# EDCPSUMK1-RP2040.net
KiCad netlist of a schematic drawn in EAGLE
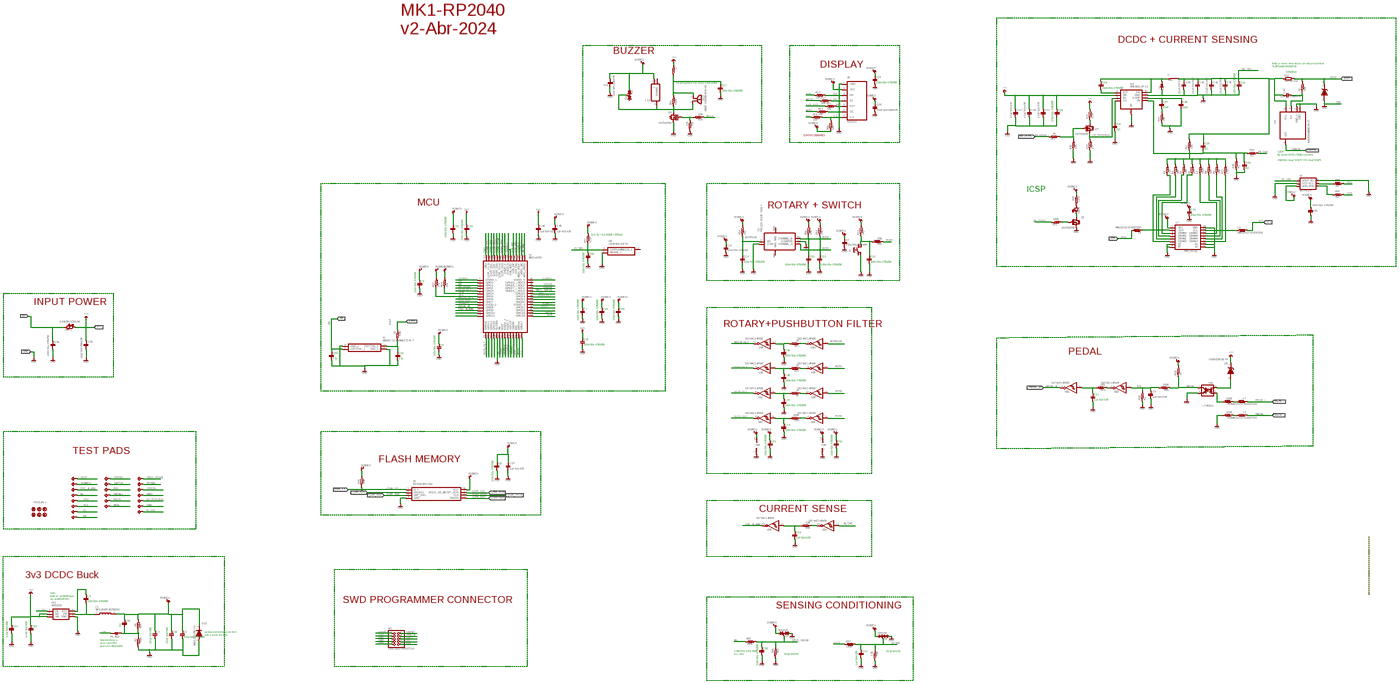
[diagram p0: schematic, sheet 1, overview]
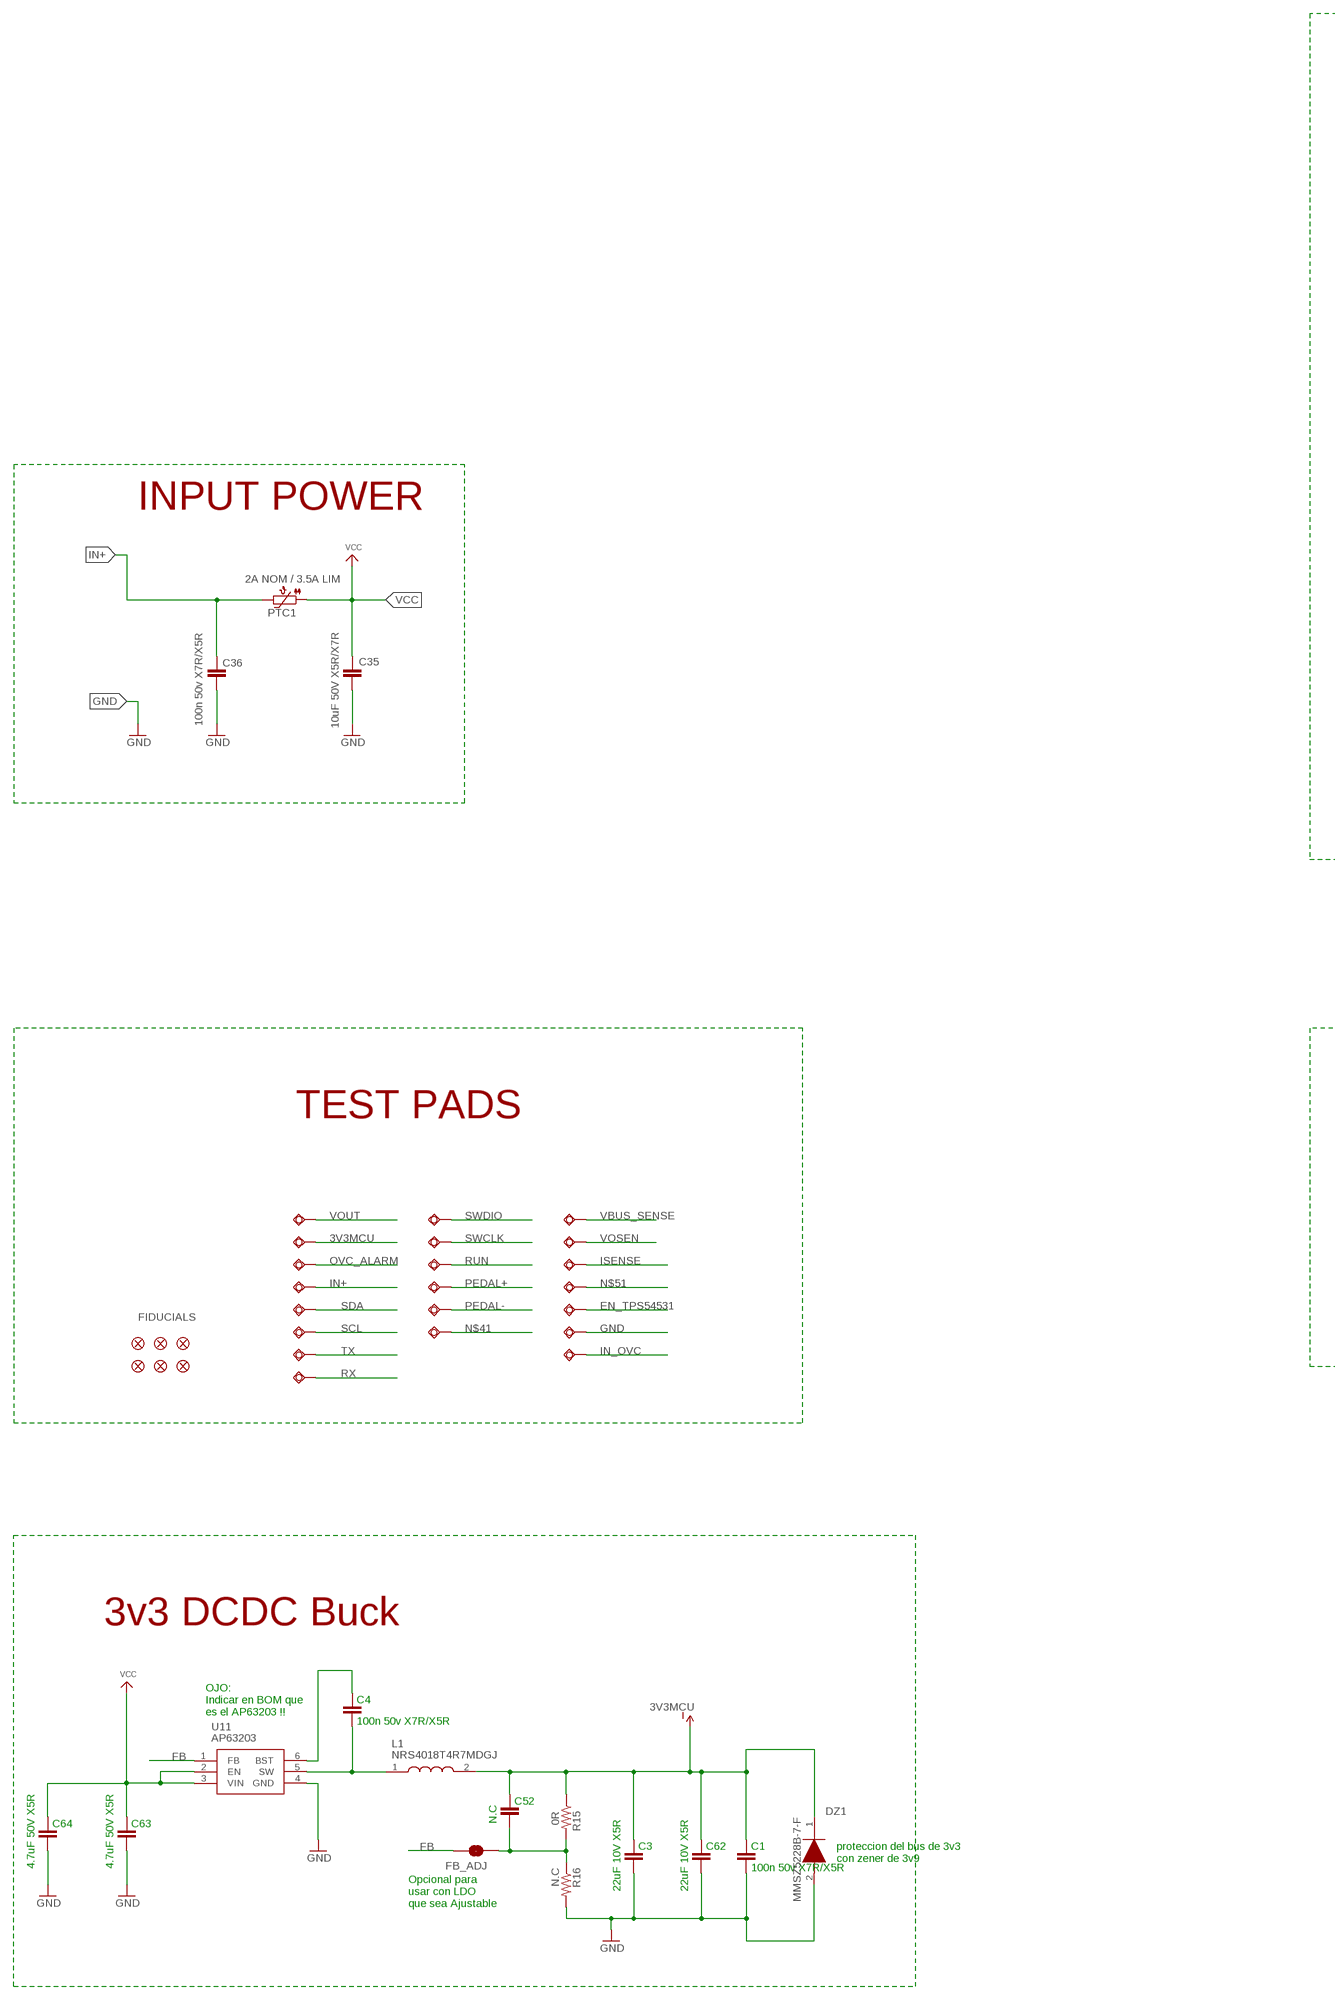
[diagram p1: schematic, sheet 1, part 1 of 5]
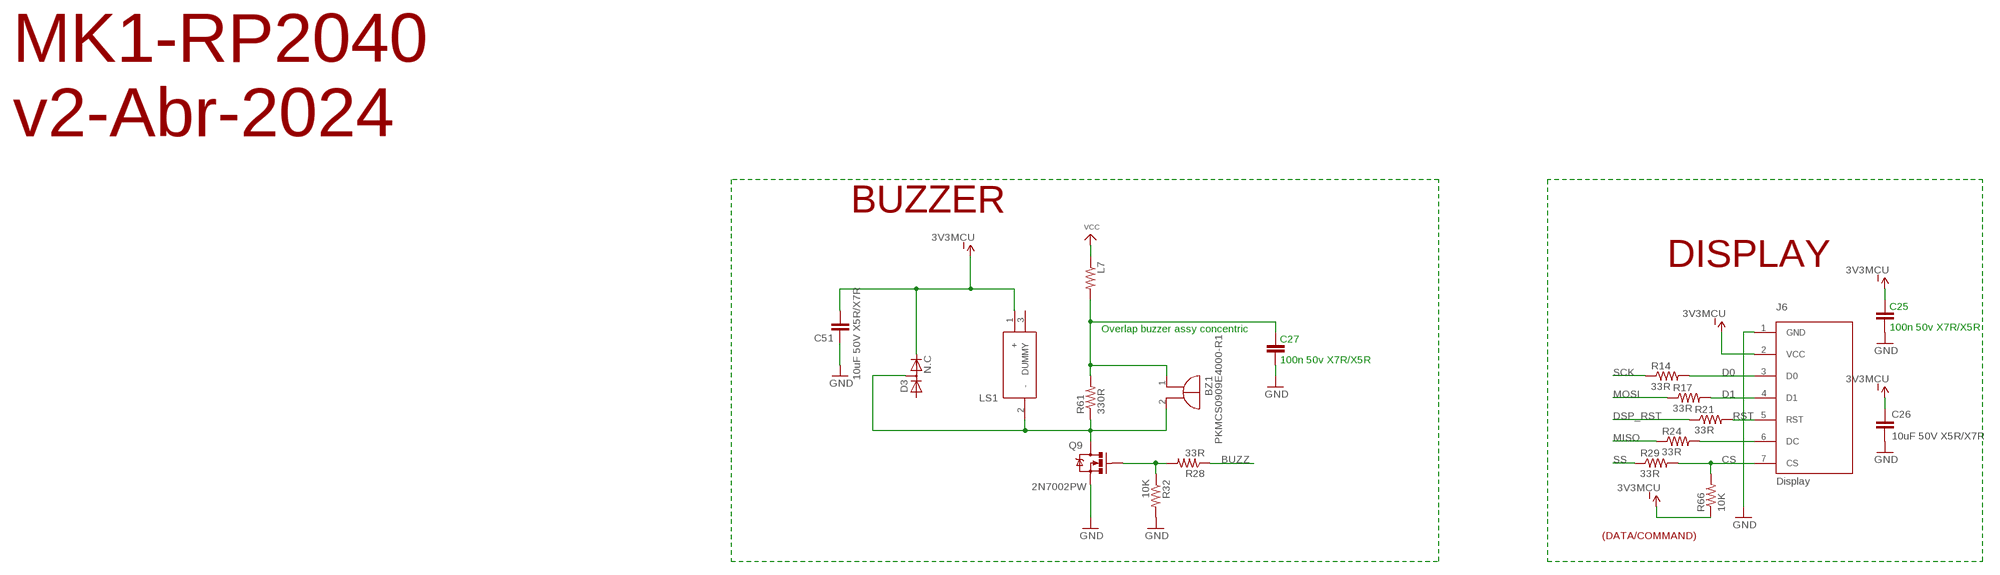
[diagram p2: schematic, sheet 1, part 2 of 5]
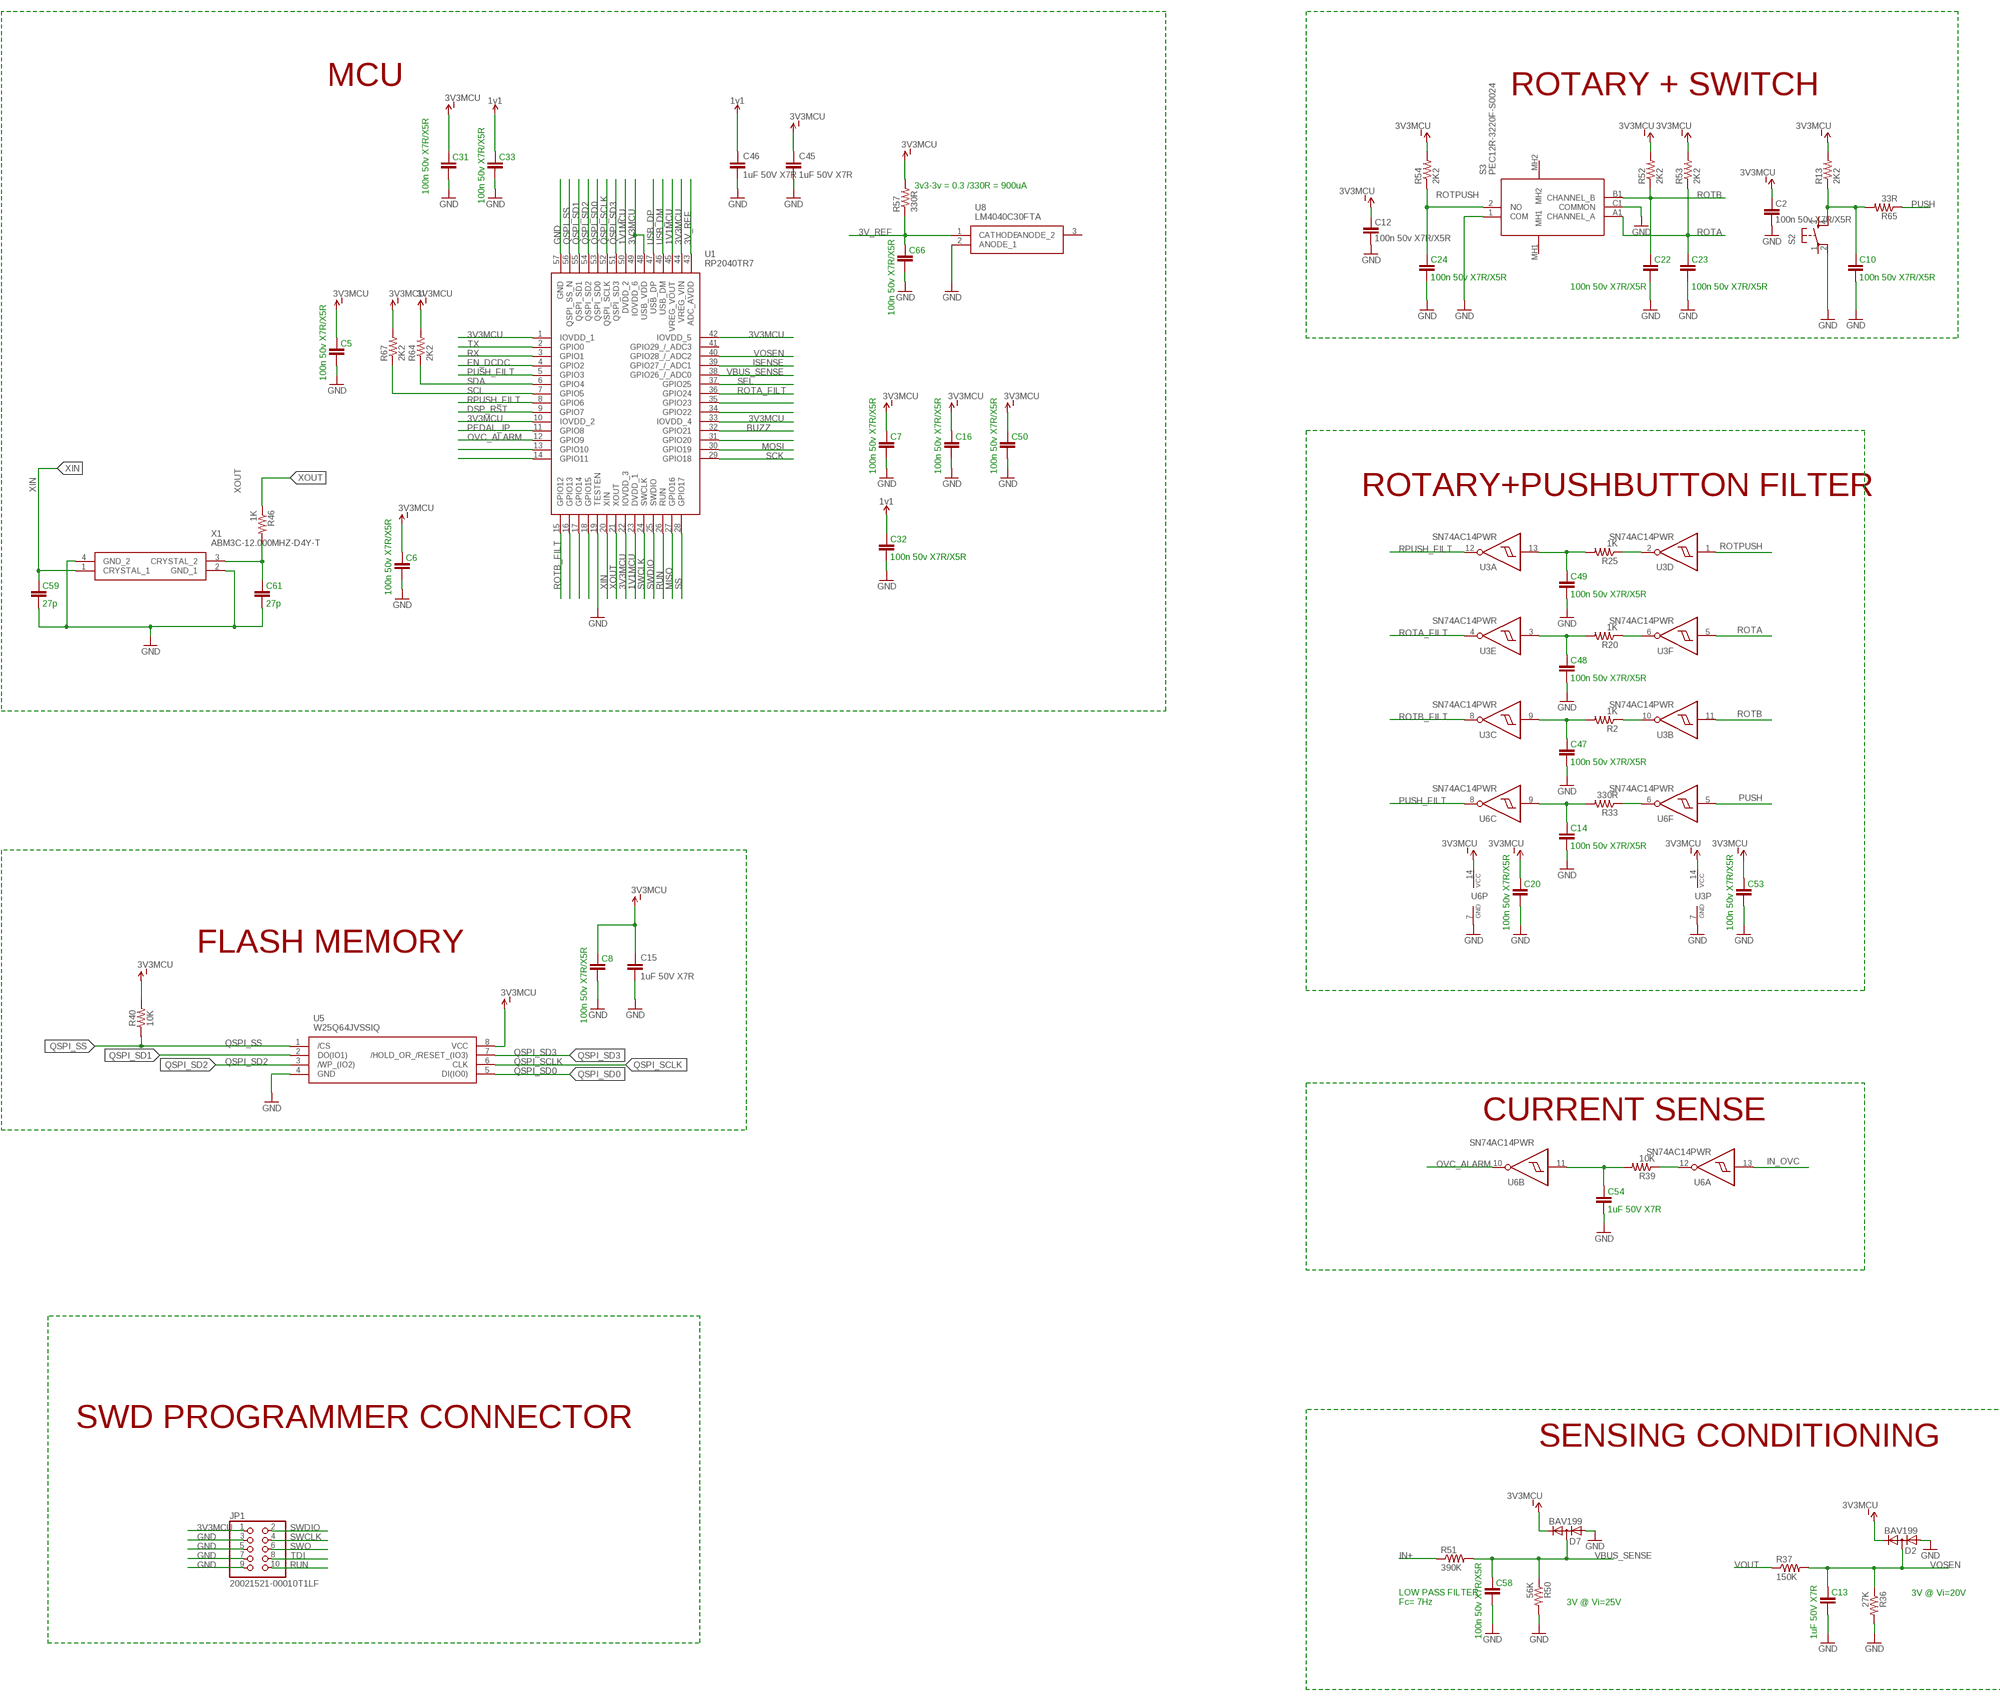
[diagram p3: schematic, sheet 1, part 3 of 5]
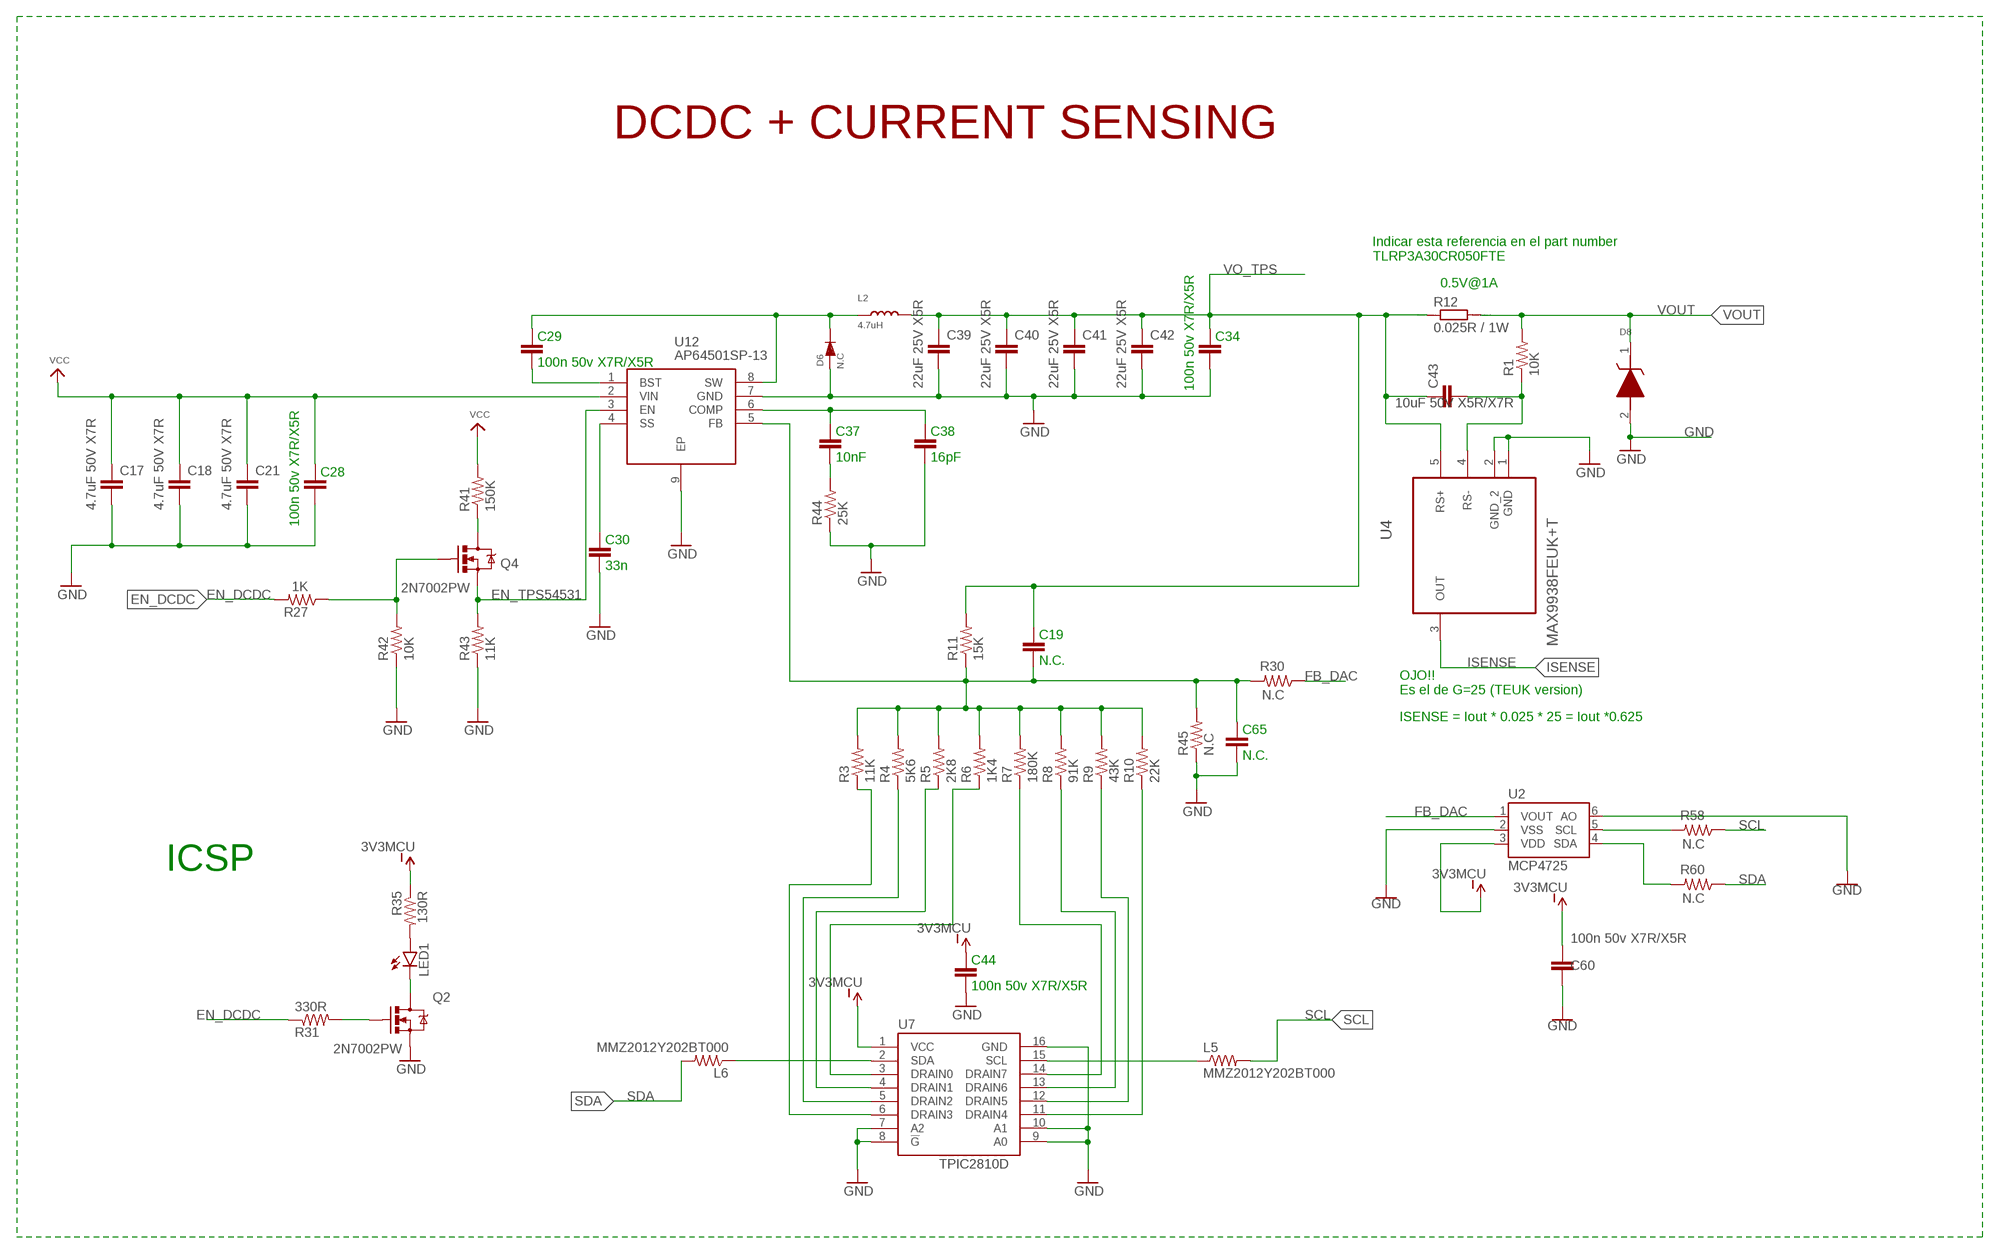
[diagram p4: schematic, sheet 1, part 4 of 5]
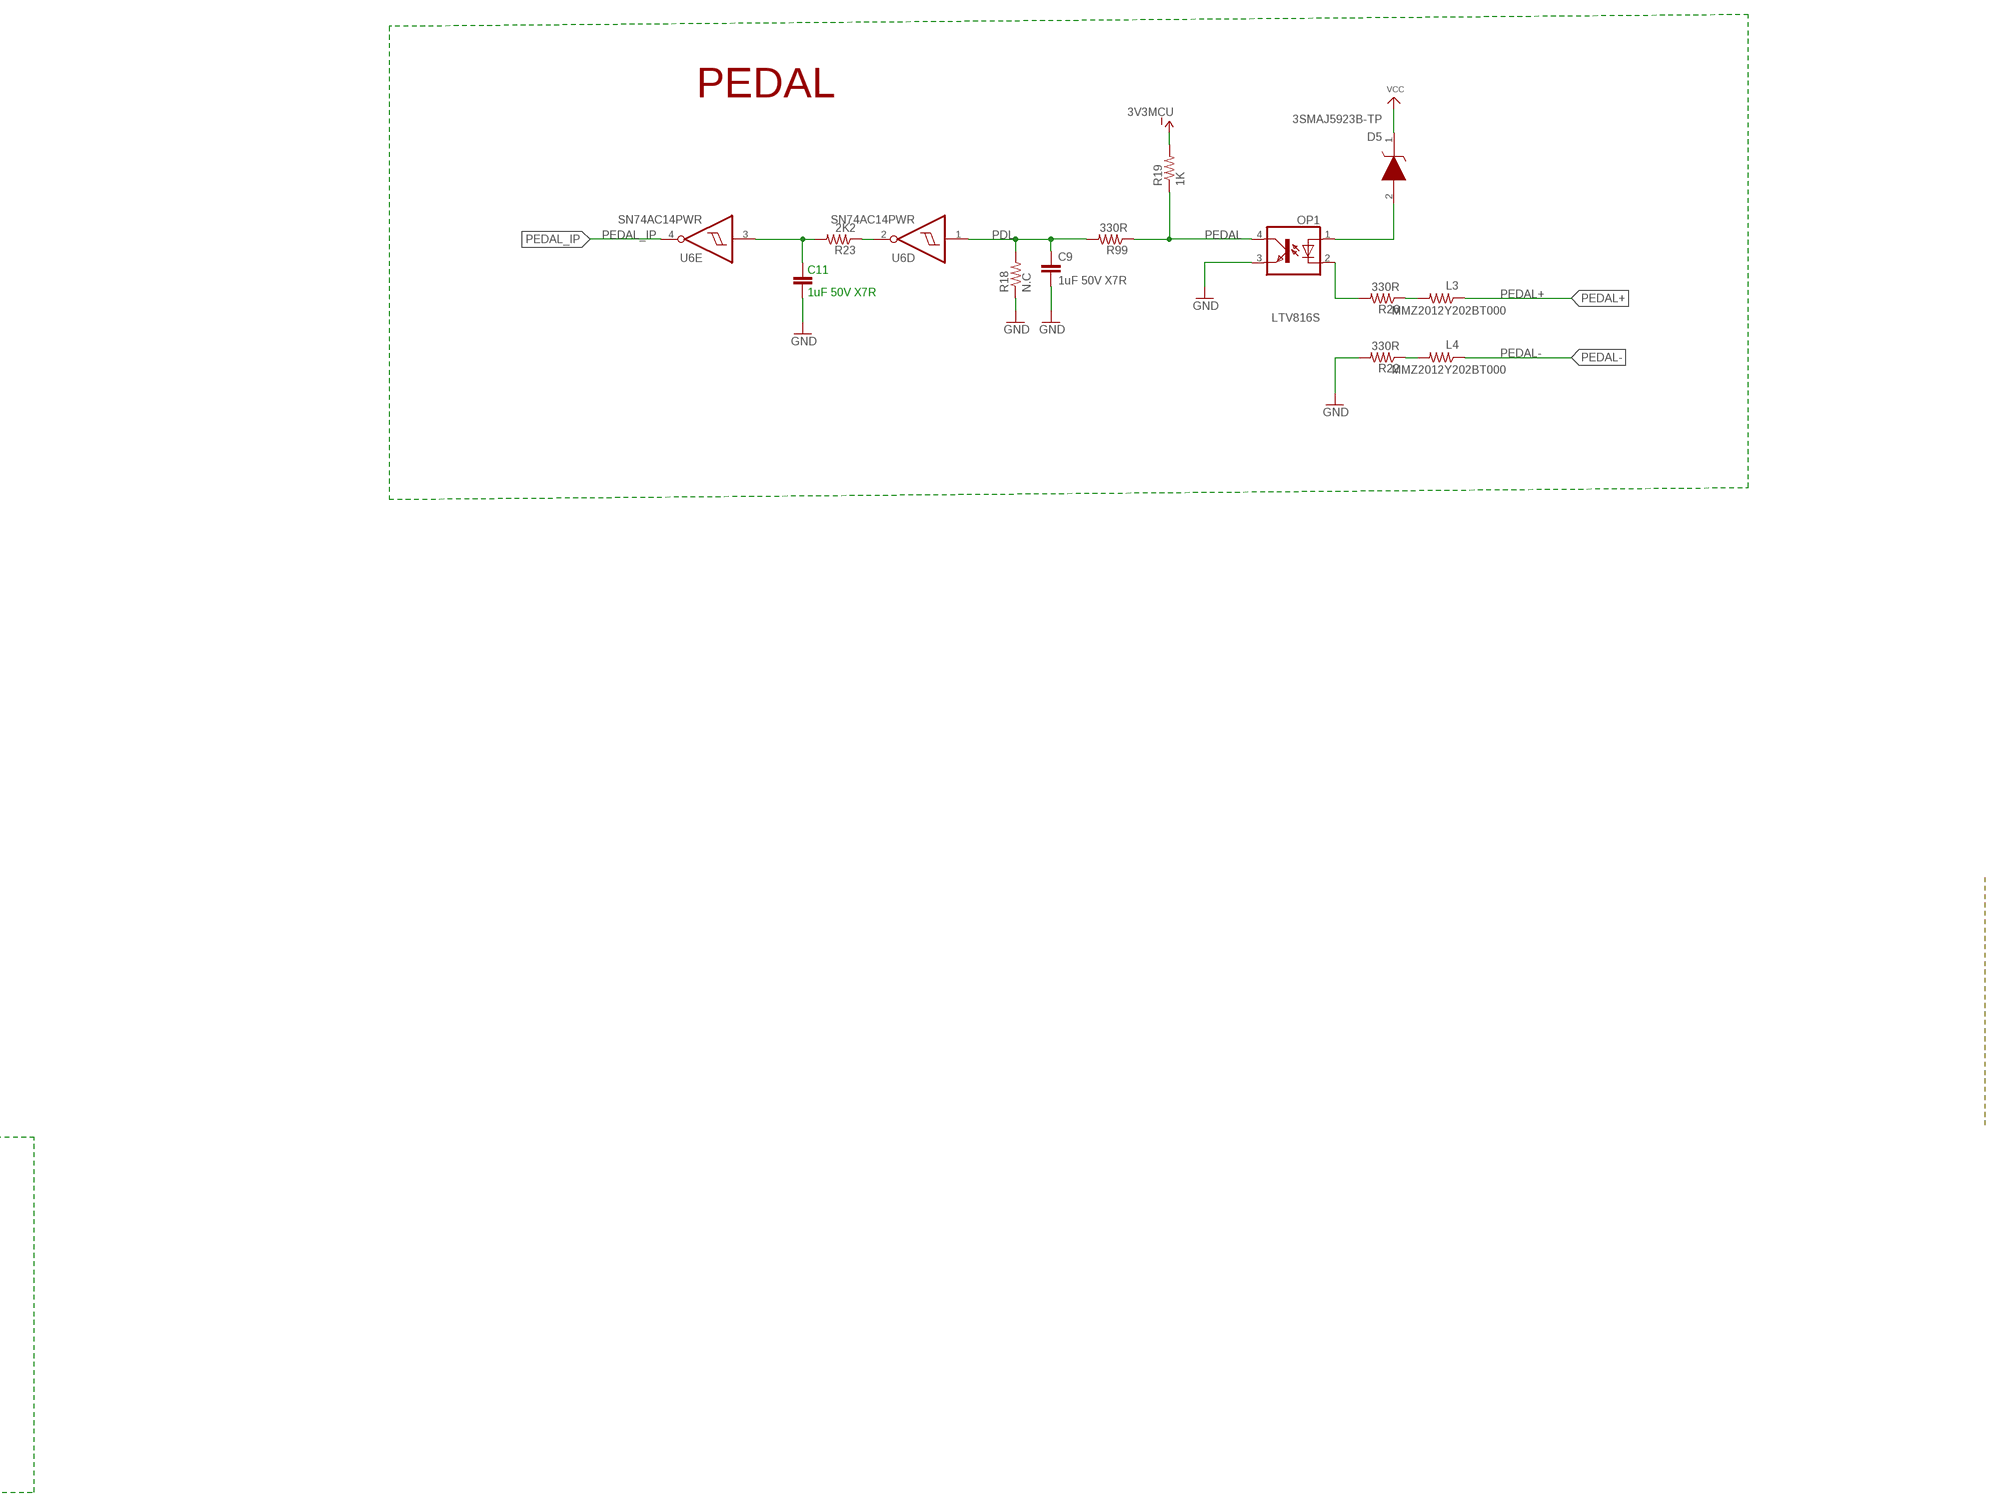
[diagram p5: schematic, sheet 1, part 5 of 5]

(export (version "E")
  (design (tool "Eeschema 10.0.6"))
  (components
    (comp (ref "3V3MCU")
      (value "TESTPAD_TPSQB1,27")
      (footprint "eagle-import:TESTPAD_B1,27")
      (libsource (lib "eagle-import") (part "TESTPAD_TPSQB1,27"))
    )
    (comp (ref "BZ1")
      (value "PKMCS0909E4000-R1")
      (footprint "eagle-import:PKMCS0909")
      (libsource (lib "eagle-import") (part "PKMCS0909E4000-R1"))
    )
    (comp (ref "C1")
      (value "100n 50v X7R/X5R")
      (footprint "eagle-import:0805")
      (libsource (lib "eagle-import") (part "CAP0805"))
    )
    (comp (ref "C2")
      (value "100n 50v X7R/X5R")
      (footprint "eagle-import:0805")
      (libsource (lib "eagle-import") (part "CAP0805"))
    )
    (comp (ref "C3")
      (value "22uF 10V X5R")
      (footprint "eagle-import:0805")
      (libsource (lib "eagle-import") (part "CAP0805"))
    )
    (comp (ref "C4")
      (value "100n 50v X7R/X5R")
      (footprint "eagle-import:0805")
      (libsource (lib "eagle-import") (part "CAP0805"))
    )
    (comp (ref "C5")
      (value "100n 50v X7R/X5R")
      (footprint "eagle-import:0805")
      (libsource (lib "eagle-import") (part "CAP0805"))
    )
    (comp (ref "C6")
      (value "100n 50v X7R/X5R")
      (footprint "eagle-import:0805")
      (libsource (lib "eagle-import") (part "CAP0805"))
    )
    (comp (ref "C7")
      (value "100n 50v X7R/X5R")
      (footprint "eagle-import:0805")
      (libsource (lib "eagle-import") (part "CAP0805"))
    )
    (comp (ref "C8")
      (value "100n 50v X7R/X5R")
      (footprint "eagle-import:0805")
      (libsource (lib "eagle-import") (part "CAP0805"))
    )
    (comp (ref "C9")
      (value "1uF 50V X7R")
      (footprint "eagle-import:0805")
      (libsource (lib "eagle-import") (part "CAP0805"))
    )
    (comp (ref "C10")
      (value "100n 50v X7R/X5R")
      (footprint "eagle-import:0805")
      (libsource (lib "eagle-import") (part "CAP0805"))
    )
    (comp (ref "C11")
      (value "1uF 50V X7R")
      (footprint "eagle-import:0805")
      (libsource (lib "eagle-import") (part "CAP0805"))
    )
    (comp (ref "C12")
      (value "100n 50v X7R/X5R")
      (footprint "eagle-import:0805")
      (libsource (lib "eagle-import") (part "CAP0805"))
    )
    (comp (ref "C13")
      (value "1uF 50V X7R")
      (footprint "eagle-import:0805")
      (libsource (lib "eagle-import") (part "CAP0805"))
    )
    (comp (ref "C14")
      (value "100n 50v X7R/X5R")
      (footprint "eagle-import:0805")
      (libsource (lib "eagle-import") (part "CAP0805"))
    )
    (comp (ref "C15")
      (value "1uF 50V X7R")
      (footprint "eagle-import:0805")
      (libsource (lib "eagle-import") (part "CAP0805"))
    )
    (comp (ref "C16")
      (value "100n 50v X7R/X5R")
      (footprint "eagle-import:0805")
      (libsource (lib "eagle-import") (part "CAP0805"))
    )
    (comp (ref "C17")
      (value "4.7uF 50V X7R")
      (footprint "eagle-import:1210")
      (libsource (lib "eagle-import") (part "CAP1210"))
    )
    (comp (ref "C18")
      (value "4.7uF 50V X7R")
      (footprint "eagle-import:1210")
      (libsource (lib "eagle-import") (part "CAP1210"))
    )
    (comp (ref "C19")
      (value "N.C.")
      (footprint "eagle-import:0805")
      (libsource (lib "eagle-import") (part "CAP0805"))
    )
    (comp (ref "C20")
      (value "100n 50v X7R/X5R")
      (footprint "eagle-import:0805")
      (libsource (lib "eagle-import") (part "CAP0805"))
    )
    (comp (ref "C21")
      (value "4.7uF 50V X7R")
      (footprint "eagle-import:1210")
      (libsource (lib "eagle-import") (part "CAP1210"))
    )
    (comp (ref "C22")
      (value "100n 50v X7R/X5R")
      (footprint "eagle-import:0805")
      (libsource (lib "eagle-import") (part "CAP0805"))
    )
    (comp (ref "C23")
      (value "100n 50v X7R/X5R")
      (footprint "eagle-import:0805")
      (libsource (lib "eagle-import") (part "CAP0805"))
    )
    (comp (ref "C24")
      (value "100n 50v X7R/X5R")
      (footprint "eagle-import:0805")
      (libsource (lib "eagle-import") (part "CAP0805"))
    )
    (comp (ref "C25")
      (value "100n 50v X7R/X5R")
      (footprint "eagle-import:0805")
      (libsource (lib "eagle-import") (part "CAP0805"))
    )
    (comp (ref "C26")
      (value "10uF 50V X5R/X7R")
      (footprint "eagle-import:1206")
      (libsource (lib "eagle-import") (part "CAP1206"))
    )
    (comp (ref "C27")
      (value "100n 50v X7R/X5R")
      (footprint "eagle-import:0805")
      (libsource (lib "eagle-import") (part "CAP0805"))
    )
    (comp (ref "C28")
      (value "100n 50v X7R/X5R")
      (footprint "eagle-import:0805")
      (libsource (lib "eagle-import") (part "CAP0805"))
    )
    (comp (ref "C29")
      (value "100n 50v X7R/X5R")
      (footprint "eagle-import:0805")
      (libsource (lib "eagle-import") (part "CAP0805"))
    )
    (comp (ref "C30")
      (value "33n")
      (footprint "eagle-import:0805")
      (libsource (lib "eagle-import") (part "CAP0805"))
    )
    (comp (ref "C31")
      (value "100n 50v X7R/X5R")
      (footprint "eagle-import:0805")
      (libsource (lib "eagle-import") (part "CAP0805"))
    )
    (comp (ref "C32")
      (value "100n 50v X7R/X5R")
      (footprint "eagle-import:0805")
      (libsource (lib "eagle-import") (part "CAP0805"))
    )
    (comp (ref "C33")
      (value "100n 50v X7R/X5R")
      (footprint "eagle-import:0805")
      (libsource (lib "eagle-import") (part "CAP0805"))
    )
    (comp (ref "C34")
      (value "100n 50v X7R/X5R")
      (footprint "eagle-import:0805")
      (libsource (lib "eagle-import") (part "CAP0805"))
    )
    (comp (ref "C35")
      (value "10uF 50V X5R/X7R")
      (footprint "eagle-import:1206")
      (libsource (lib "eagle-import") (part "CAP1206"))
    )
    (comp (ref "C36")
      (value "100n 50v X7R/X5R")
      (footprint "eagle-import:0805")
      (libsource (lib "eagle-import") (part "CAP0805"))
    )
    (comp (ref "C37")
      (value "10nF")
      (footprint "eagle-import:0805")
      (libsource (lib "eagle-import") (part "CAP0805"))
    )
    (comp (ref "C38")
      (value "16pF")
      (footprint "eagle-import:0805")
      (libsource (lib "eagle-import") (part "CAP0805"))
    )
    (comp (ref "C39")
      (value "22uF 25V X5R")
      (footprint "eagle-import:1210")
      (libsource (lib "eagle-import") (part "CAP1210"))
    )
    (comp (ref "C40")
      (value "22uF 25V X5R")
      (footprint "eagle-import:1210")
      (libsource (lib "eagle-import") (part "CAP1210"))
    )
    (comp (ref "C41")
      (value "22uF 25V X5R")
      (footprint "eagle-import:1210")
      (libsource (lib "eagle-import") (part "CAP1210"))
    )
    (comp (ref "C42")
      (value "22uF 25V X5R")
      (footprint "eagle-import:1210")
      (libsource (lib "eagle-import") (part "CAP1210"))
    )
    (comp (ref "C43")
      (value "10uF 50V X5R/X7R")
      (footprint "eagle-import:1206")
      (libsource (lib "eagle-import") (part "CAP1206"))
    )
    (comp (ref "C44")
      (value "100n 50v X7R/X5R")
      (footprint "eagle-import:0805")
      (libsource (lib "eagle-import") (part "CAP0805"))
    )
    (comp (ref "C45")
      (value "1uF 50V X7R")
      (footprint "eagle-import:0805")
      (libsource (lib "eagle-import") (part "CAP0805"))
    )
    (comp (ref "C46")
      (value "1uF 50V X7R")
      (footprint "eagle-import:0805")
      (libsource (lib "eagle-import") (part "CAP0805"))
    )
    (comp (ref "C47")
      (value "100n 50v X7R/X5R")
      (footprint "eagle-import:0805")
      (libsource (lib "eagle-import") (part "CAP0805"))
    )
    (comp (ref "C48")
      (value "100n 50v X7R/X5R")
      (footprint "eagle-import:0805")
      (libsource (lib "eagle-import") (part "CAP0805"))
    )
    (comp (ref "C49")
      (value "100n 50v X7R/X5R")
      (footprint "eagle-import:0805")
      (libsource (lib "eagle-import") (part "CAP0805"))
    )
    (comp (ref "C50")
      (value "100n 50v X7R/X5R")
      (footprint "eagle-import:0805")
      (libsource (lib "eagle-import") (part "CAP0805"))
    )
    (comp (ref "C51")
      (value "10uF 50V X5R/X7R")
      (footprint "eagle-import:1206")
      (libsource (lib "eagle-import") (part "CAP1206"))
    )
    (comp (ref "C52")
      (value "N.C")
      (footprint "eagle-import:0805")
      (libsource (lib "eagle-import") (part "CAP0805"))
    )
    (comp (ref "C53")
      (value "100n 50v X7R/X5R")
      (footprint "eagle-import:0805")
      (libsource (lib "eagle-import") (part "CAP0805"))
    )
    (comp (ref "C54")
      (value "1uF 50V X7R")
      (footprint "eagle-import:0805")
      (libsource (lib "eagle-import") (part "CAP0805"))
    )
    (comp (ref "C58")
      (value "100n 50v X7R/X5R")
      (footprint "eagle-import:0805")
      (libsource (lib "eagle-import") (part "CAP0805"))
    )
    (comp (ref "C59")
      (value "27p")
      (footprint "eagle-import:0805")
      (libsource (lib "eagle-import") (part "CAP0805"))
    )
    (comp (ref "C60")
      (value "100n 50v X7R/X5R")
      (footprint "eagle-import:0805")
      (libsource (lib "eagle-import") (part "CAP0805"))
    )
    (comp (ref "C61")
      (value "27p")
      (footprint "eagle-import:0805")
      (libsource (lib "eagle-import") (part "CAP0805"))
    )
    (comp (ref "C62")
      (value "22uF 10V X5R")
      (footprint "eagle-import:0805")
      (libsource (lib "eagle-import") (part "CAP0805"))
    )
    (comp (ref "C63")
      (value "4.7uF 50V X5R")
      (footprint "eagle-import:0805")
      (libsource (lib "eagle-import") (part "CAP0805"))
    )
    (comp (ref "C64")
      (value "4.7uF 50V X5R")
      (footprint "eagle-import:0805")
      (libsource (lib "eagle-import") (part "CAP0805"))
    )
    (comp (ref "C65")
      (value "N.C.")
      (footprint "eagle-import:0805")
      (libsource (lib "eagle-import") (part "CAP0805"))
    )
    (comp (ref "C66")
      (value "100n 50v X7R/X5R")
      (footprint "eagle-import:0805")
      (libsource (lib "eagle-import") (part "CAP0805"))
    )
    (comp (ref "D2")
      (value "BAV199")
      (footprint "eagle-import:SOT23")
      (libsource (lib "eagle-import") (part "BAV199"))
    )
    (comp (ref "D3")
      (value "N.C")
      (footprint "eagle-import:SOT23")
      (libsource (lib "eagle-import") (part "BAV199"))
    )
    (comp (ref "D5")
      (value "3SMAJ5923B-TP")
      (footprint "eagle-import:DIOM5226X244N")
      (fields (field (name "MOUSER_PART_NUMBER") "833-3SMAJ5923B-TP"))
      (libsource (lib "eagle-import") (part "3SMAJ5923B-TP"))
    )
    (comp (ref "D6")
      (value "N.C")
      (footprint "eagle-import:DO-214AB")
      (libsource (lib "eagle-import") (part "DSMC"))
    )
    (comp (ref "D7")
      (value "BAV199")
      (footprint "eagle-import:SOT23")
      (libsource (lib "eagle-import") (part "BAV199"))
    )
    (comp (ref "D8")
      (value "RB060M-60TR")
      (footprint "eagle-import:DIOM5226X244N")
      (fields
        (field (name "ARROW_PART_NUMBER") "3SMAJ5923B-TP")
        (field (name "MOUSER_PART_NUMBER") "833-3SMAJ5923B-TP")
      )
      (libsource (lib "eagle-import") (part "3SMAJ5923B-TP"))
    )
    (comp (ref "DZ1")
      (value "MMSZ5228B-7-F")
      (footprint "eagle-import:SODFL3518X115N")
      (libsource (lib "eagle-import") (part "MMSZ5228B-7-F"))
    )
    (comp (ref "EN_TPS54531")
      (value "TESTPAD_TPSQB1,27")
      (footprint "eagle-import:TESTPAD_B1,27")
      (libsource (lib "eagle-import") (part "TESTPAD_TPSQB1,27"))
    )
    (comp (ref "FB_ADJ")
      (value "JUMPER-SMT_2_NC_TRACE_NO-SILK")
      (footprint "eagle-import:SMT-JUMPER_2_NC_TRACE_NO-SILK")
      (libsource (lib "eagle-import") (part "JUMPER-SMT_2_NC_TRACE_NO-SILK"))
    )
    (comp (ref "FID1")
      (value "FIDUCIAL1X2")
      (footprint "eagle-import:FIDUCIAL-1X2")
      (libsource (lib "eagle-import") (part "FIDUCIAL1X2"))
    )
    (comp (ref "FID2")
      (value "FIDUCIAL1X2")
      (footprint "eagle-import:FIDUCIAL-1X2")
      (libsource (lib "eagle-import") (part "FIDUCIAL1X2"))
    )
    (comp (ref "FID3")
      (value "FIDUCIAL1X2")
      (footprint "eagle-import:FIDUCIAL-1X2")
      (libsource (lib "eagle-import") (part "FIDUCIAL1X2"))
    )
    (comp (ref "FID4")
      (value "FIDUCIAL1X2")
      (footprint "eagle-import:FIDUCIAL-1X2")
      (libsource (lib "eagle-import") (part "FIDUCIAL1X2"))
    )
    (comp (ref "FID5")
      (value "FIDUCIAL1X2")
      (footprint "eagle-import:FIDUCIAL-1X2")
      (libsource (lib "eagle-import") (part "FIDUCIAL1X2"))
    )
    (comp (ref "FID6")
      (value "FIDUCIAL1X2")
      (footprint "eagle-import:FIDUCIAL-1X2")
      (libsource (lib "eagle-import") (part "FIDUCIAL1X2"))
    )
    (comp (ref "GND")
      (value "TESTPAD_TPSQB1,27")
      (footprint "eagle-import:TESTPAD_B1,27")
      (libsource (lib "eagle-import") (part "TESTPAD_TPSQB1,27"))
    )
    (comp (ref "IN+")
      (value "TESTPAD_TPSQB1,27")
      (footprint "eagle-import:TESTPAD_B1,27")
      (libsource (lib "eagle-import") (part "TESTPAD_TPSQB1,27"))
    )
    (comp (ref "IN_OVC")
      (value "TESTPAD_TPSQB1,27")
      (footprint "eagle-import:TESTPAD_B1,27")
      (libsource (lib "eagle-import") (part "TESTPAD_TPSQB1,27"))
    )
    (comp (ref "ISENSE")
      (value "TESTPAD_TPSQB1,27")
      (footprint "eagle-import:TESTPAD_B1,27")
      (libsource (lib "eagle-import") (part "TESTPAD_TPSQB1,27"))
    )
    (comp (ref "J6")
      (value "Display")
      (footprint "eagle-import:OLED_LCD")
      (libsource (lib "eagle-import") (part "OLED_LCD"))
    )
    (comp (ref "JP1")
      (value "20021521-00010T1LF")
      (footprint "eagle-import:20021521-00010T1LF")
      (fields (field (name "DIGI-KEY_PART_NUMBER") "609-4054-ND") (field (name "MF") "AMPHENOL ICC / FCI"))
      (libsource (lib "eagle-import") (part "20021521-00010T1LF"))
    )
    (comp (ref "L1")
      (value "NRS4018T4R7MDGJ")
      (footprint "eagle-import:NRS4018T100MDGJ")
      (fields (field (name "MOUSER_PART_NUMBER") "963-NRS4018T4R7MDGJ"))
      (libsource (lib "eagle-import") (part "NRS4018T4R7MDGJ"))
    )
    (comp (ref "L2")
      (value "4.7uH")
      (footprint "eagle-import:WE-LHMI")
      (libsource (lib "eagle-import") (part "L74437368047"))
    )
    (comp (ref "L3")
      (value "MMZ2012Y202BT000")
      (footprint "eagle-import:0805")
      (libsource (lib "eagle-import") (part "RESISTOR0805-RES"))
    )
    (comp (ref "L4")
      (value "MMZ2012Y202BT000")
      (footprint "eagle-import:0805")
      (libsource (lib "eagle-import") (part "RESISTOR0805-RES"))
    )
    (comp (ref "L5")
      (value "MMZ2012Y202BT000")
      (footprint "eagle-import:0805")
      (libsource (lib "eagle-import") (part "RESISTOR0805-RES"))
    )
    (comp (ref "L6")
      (value "MMZ2012Y202BT000")
      (footprint "eagle-import:0805")
      (libsource (lib "eagle-import") (part "RESISTOR0805-RES"))
    )
    (comp (ref "L7")
      (value "MMZ2012Y202BT000")
      (footprint "eagle-import:0805")
      (libsource (lib "eagle-import") (part "RESISTOR0805-RES"))
    )
    (comp (ref "LED1")
      (value "LED3MM")
      (footprint "eagle-import:LED3MM")
      (libsource (lib "eagle-import") (part "LED3MM"))
    )
    (comp (ref "LS1")
      (value "SMT-0540-S-R")
      (footprint "eagle-import:SMT0540SR")
      (fields (field (name "MOUSER_PART_NUMBER") "665-SMT0540SR"))
      (libsource (lib "eagle-import") (part "SMT-0540-S-R"))
    )
    (comp (ref "N$41")
      (value "TESTPAD_TPSQB1,27")
      (footprint "eagle-import:TESTPAD_B1,27")
      (libsource (lib "eagle-import") (part "TESTPAD_TPSQB1,27"))
    )
    (comp (ref "N$51")
      (value "TESTPAD_TPSQB1,27")
      (footprint "eagle-import:TESTPAD_B1,27")
      (libsource (lib "eagle-import") (part "TESTPAD_TPSQB1,27"))
    )
    (comp (ref "OP1")
      (value "LTV816S")
      (footprint "eagle-import:SMD4")
      (libsource (lib "eagle-import") (part "LTV816S"))
    )
    (comp (ref "OVC_ALARM")
      (value "TESTPAD_TPSQB1,27")
      (footprint "eagle-import:TESTPAD_B1,27")
      (libsource (lib "eagle-import") (part "TESTPAD_TPSQB1,27"))
    )
    (comp (ref "PEDAL+")
      (value "TESTPAD_TPSQB1,27")
      (footprint "eagle-import:TESTPAD_B1,27")
      (libsource (lib "eagle-import") (part "TESTPAD_TPSQB1,27"))
    )
    (comp (ref "PEDAL-")
      (value "TESTPAD_TPSQB1,27")
      (footprint "eagle-import:TESTPAD_B1,27")
      (libsource (lib "eagle-import") (part "TESTPAD_TPSQB1,27"))
    )
    (comp (ref "PTC1")
      (value "2A NOM / 3.5A LIM")
      (footprint "eagle-import:1812L")
      (libsource (lib "eagle-import") (part "PTC-"))
    )
    (comp (ref "Q2")
      (value "2N7002PW")
      (footprint "eagle-import:SOT323")
      (libsource (lib "eagle-import") (part "MOSFET-NCHANNEL2N7002PW"))
    )
    (comp (ref "Q4")
      (value "2N7002PW")
      (footprint "eagle-import:SOT323")
      (libsource (lib "eagle-import") (part "MOSFET-NCHANNEL2N7002PW"))
    )
    (comp (ref "Q9")
      (value "2N7002PW")
      (footprint "eagle-import:SOT323")
      (libsource (lib "eagle-import") (part "MOSFET-NCHANNEL2N7002PW"))
    )
    (comp (ref "R1")
      (value "10K")
      (footprint "eagle-import:0805")
      (libsource (lib "eagle-import") (part "RESISTOR0805"))
    )
    (comp (ref "R2")
      (value "1K")
      (footprint "eagle-import:0805")
      (libsource (lib "eagle-import") (part "RESISTOR0805"))
    )
    (comp (ref "R3")
      (value "11K")
      (footprint "eagle-import:0805")
      (libsource (lib "eagle-import") (part "RESISTOR0805"))
    )
    (comp (ref "R4")
      (value "5K6")
      (footprint "eagle-import:0805")
      (libsource (lib "eagle-import") (part "RESISTOR0805"))
    )
    (comp (ref "R5")
      (value "2K8")
      (footprint "eagle-import:0805")
      (libsource (lib "eagle-import") (part "RESISTOR0805"))
    )
    (comp (ref "R6")
      (value "1K4")
      (footprint "eagle-import:0805")
      (libsource (lib "eagle-import") (part "RESISTOR0805"))
    )
    (comp (ref "R7")
      (value "180K")
      (footprint "eagle-import:0805")
      (libsource (lib "eagle-import") (part "RESISTOR0805"))
    )
    (comp (ref "R8")
      (value "91K")
      (footprint "eagle-import:0805")
      (libsource (lib "eagle-import") (part "RESISTOR0805"))
    )
    (comp (ref "R9")
      (value "43K")
      (footprint "eagle-import:0805")
      (libsource (lib "eagle-import") (part "RESISTOR0805"))
    )
    (comp (ref "R10")
      (value "22K")
      (footprint "eagle-import:0805")
      (libsource (lib "eagle-import") (part "RESISTOR0805"))
    )
    (comp (ref "R11")
      (value "15K")
      (footprint "eagle-import:0805")
      (libsource (lib "eagle-import") (part "RESISTOR0805"))
    )
    (comp (ref "R12")
      (value "0.025R / 1W")
      (footprint "eagle-import:R2512")
      (libsource (lib "eagle-import") (part "RR2512"))
    )
    (comp (ref "R13")
      (value "2K2")
      (footprint "eagle-import:0805")
      (libsource (lib "eagle-import") (part "RESISTOR0805"))
    )
    (comp (ref "R14")
      (value "33R")
      (footprint "eagle-import:0805")
      (libsource (lib "eagle-import") (part "RESISTOR0805"))
    )
    (comp (ref "R15")
      (value "0R")
      (footprint "eagle-import:0805")
      (libsource (lib "eagle-import") (part "RESISTOR0805"))
    )
    (comp (ref "R16")
      (value "N.C")
      (footprint "eagle-import:0805")
      (libsource (lib "eagle-import") (part "RESISTOR0805"))
    )
    (comp (ref "R17")
      (value "33R")
      (footprint "eagle-import:0805")
      (libsource (lib "eagle-import") (part "RESISTOR0805"))
    )
    (comp (ref "R18")
      (value "N.C")
      (footprint "eagle-import:0805")
      (libsource (lib "eagle-import") (part "RESISTOR0805"))
    )
    (comp (ref "R19")
      (value "1K")
      (footprint "eagle-import:0805")
      (libsource (lib "eagle-import") (part "RESISTOR0805"))
    )
    (comp (ref "R20")
      (value "1K")
      (footprint "eagle-import:0805")
      (libsource (lib "eagle-import") (part "RESISTOR0805"))
    )
    (comp (ref "R21")
      (value "33R")
      (footprint "eagle-import:0805")
      (libsource (lib "eagle-import") (part "RESISTOR0805"))
    )
    (comp (ref "R22")
      (value "330R")
      (footprint "eagle-import:0805")
      (libsource (lib "eagle-import") (part "RESISTOR0805"))
    )
    (comp (ref "R23")
      (value "2K2")
      (footprint "eagle-import:0805")
      (libsource (lib "eagle-import") (part "RESISTOR0805"))
    )
    (comp (ref "R24")
      (value "33R")
      (footprint "eagle-import:0805")
      (libsource (lib "eagle-import") (part "RESISTOR0805"))
    )
    (comp (ref "R25")
      (value "1K")
      (footprint "eagle-import:0805")
      (libsource (lib "eagle-import") (part "RESISTOR0805"))
    )
    (comp (ref "R26")
      (value "330R")
      (footprint "eagle-import:0805")
      (libsource (lib "eagle-import") (part "RESISTOR0805"))
    )
    (comp (ref "R27")
      (value "1K")
      (footprint "eagle-import:0805")
      (libsource (lib "eagle-import") (part "RESISTOR0805"))
    )
    (comp (ref "R28")
      (value "33R")
      (footprint "eagle-import:0805")
      (libsource (lib "eagle-import") (part "RESISTOR0805"))
    )
    (comp (ref "R29")
      (value "33R")
      (footprint "eagle-import:0805")
      (libsource (lib "eagle-import") (part "RESISTOR0805"))
    )
    (comp (ref "R30")
      (value "N.C")
      (footprint "eagle-import:0805")
      (libsource (lib "eagle-import") (part "RESISTOR0805"))
    )
    (comp (ref "R31")
      (value "330R")
      (footprint "eagle-import:0805")
      (libsource (lib "eagle-import") (part "RESISTOR0805"))
    )
    (comp (ref "R32")
      (value "10K")
      (footprint "eagle-import:0805")
      (libsource (lib "eagle-import") (part "RESISTOR0805"))
    )
    (comp (ref "R33")
      (value "330R")
      (footprint "eagle-import:0805")
      (libsource (lib "eagle-import") (part "RESISTOR0805"))
    )
    (comp (ref "R35")
      (value "130R")
      (footprint "eagle-import:0805")
      (libsource (lib "eagle-import") (part "RESISTOR0805"))
    )
    (comp (ref "R36")
      (value "27K")
      (footprint "eagle-import:0805")
      (libsource (lib "eagle-import") (part "RESISTOR0805"))
    )
    (comp (ref "R37")
      (value "150K")
      (footprint "eagle-import:0805")
      (libsource (lib "eagle-import") (part "RESISTOR0805"))
    )
    (comp (ref "R39")
      (value "10K")
      (footprint "eagle-import:0805")
      (libsource (lib "eagle-import") (part "RESISTOR0805"))
    )
    (comp (ref "R40")
      (value "10K")
      (footprint "eagle-import:0805")
      (libsource (lib "eagle-import") (part "RESISTOR0805"))
    )
    (comp (ref "R41")
      (value "150K")
      (footprint "eagle-import:0805")
      (libsource (lib "eagle-import") (part "RESISTOR0805"))
    )
    (comp (ref "R42")
      (value "10K")
      (footprint "eagle-import:0805")
      (libsource (lib "eagle-import") (part "RESISTOR0805"))
    )
    (comp (ref "R43")
      (value "11K")
      (footprint "eagle-import:0805")
      (libsource (lib "eagle-import") (part "RESISTOR0805"))
    )
    (comp (ref "R44")
      (value "25K")
      (footprint "eagle-import:0805")
      (libsource (lib "eagle-import") (part "RESISTOR0805"))
    )
    (comp (ref "R45")
      (value "N.C")
      (footprint "eagle-import:0805")
      (libsource (lib "eagle-import") (part "RESISTOR0805"))
    )
    (comp (ref "R46")
      (value "1K")
      (footprint "eagle-import:0805")
      (libsource (lib "eagle-import") (part "RESISTOR0805"))
    )
    (comp (ref "R50")
      (value "56K")
      (footprint "eagle-import:0805")
      (libsource (lib "eagle-import") (part "RESISTOR0805"))
    )
    (comp (ref "R51")
      (value "390K")
      (footprint "eagle-import:0805")
      (libsource (lib "eagle-import") (part "RESISTOR0805"))
    )
    (comp (ref "R52")
      (value "2K2")
      (footprint "eagle-import:0805")
      (libsource (lib "eagle-import") (part "RESISTOR0805"))
    )
    (comp (ref "R53")
      (value "2K2")
      (footprint "eagle-import:0805")
      (libsource (lib "eagle-import") (part "RESISTOR0805"))
    )
    (comp (ref "R54")
      (value "2K2")
      (footprint "eagle-import:0805")
      (libsource (lib "eagle-import") (part "RESISTOR0805"))
    )
    (comp (ref "R57")
      (value "330R")
      (footprint "eagle-import:0805")
      (libsource (lib "eagle-import") (part "RESISTOR0805"))
    )
    (comp (ref "R58")
      (value "N.C")
      (footprint "eagle-import:0805")
      (libsource (lib "eagle-import") (part "RESISTOR0805"))
    )
    (comp (ref "R60")
      (value "N.C")
      (footprint "eagle-import:0805")
      (libsource (lib "eagle-import") (part "RESISTOR0805"))
    )
    (comp (ref "R61")
      (value "330R")
      (footprint "eagle-import:0805")
      (libsource (lib "eagle-import") (part "RESISTOR0805"))
    )
    (comp (ref "R64")
      (value "2K2")
      (footprint "eagle-import:0805")
      (libsource (lib "eagle-import") (part "RESISTOR0805"))
    )
    (comp (ref "R65")
      (value "33R")
      (footprint "eagle-import:0805")
      (libsource (lib "eagle-import") (part "RESISTOR0805"))
    )
    (comp (ref "R66")
      (value "10K")
      (footprint "eagle-import:0805")
      (libsource (lib "eagle-import") (part "RESISTOR0805"))
    )
    (comp (ref "R67")
      (value "2K2")
      (footprint "eagle-import:0805")
      (libsource (lib "eagle-import") (part "RESISTOR0805"))
    )
    (comp (ref "R99")
      (value "330R")
      (footprint "eagle-import:0805")
      (libsource (lib "eagle-import") (part "RESISTOR0805"))
    )
    (comp (ref "RUN")
      (value "TESTPAD_TPSQB1,27")
      (footprint "eagle-import:TESTPAD_B1,27")
      (libsource (lib "eagle-import") (part "TESTPAD_TPSQB1,27"))
    )
    (comp (ref "RX")
      (value "TESTPAD_TPSQB1,27")
      (footprint "eagle-import:TESTPAD_B1,27")
      (libsource (lib "eagle-import") (part "TESTPAD_TPSQB1,27"))
    )
    (comp (ref "S2")
      (value "TAC_SWITCH_KSC931G-SMD")
      (footprint "eagle-import:TAC_SW_SMD_KSC931G")
      (libsource (lib "eagle-import") (part "TAC_SWITCH_KSC931G-SMD"))
    )
    (comp (ref "S3")
      (value "PEC12R-3220F-S0024")
      (footprint "eagle-import:PEC12R3220FS0024")
      (fields (field (name "MOUSER_PART_NUMBER") "652-PEC12R3220FS0024"))
      (libsource (lib "eagle-import") (part "PEC12R-3220F-S0024"))
    )
    (comp (ref "SCL")
      (value "TESTPAD_TPSQB1,27")
      (footprint "eagle-import:TESTPAD_B1,27")
      (libsource (lib "eagle-import") (part "TESTPAD_TPSQB1,27"))
    )
    (comp (ref "SDA")
      (value "TESTPAD_TPSQB1,27")
      (footprint "eagle-import:TESTPAD_B1,27")
      (libsource (lib "eagle-import") (part "TESTPAD_TPSQB1,27"))
    )
    (comp (ref "SWCLK")
      (value "TESTPAD_TPSQB1,27")
      (footprint "eagle-import:TESTPAD_B1,27")
      (libsource (lib "eagle-import") (part "TESTPAD_TPSQB1,27"))
    )
    (comp (ref "SWDIO")
      (value "TESTPAD_TPSQB1,27")
      (footprint "eagle-import:TESTPAD_B1,27")
      (libsource (lib "eagle-import") (part "TESTPAD_TPSQB1,27"))
    )
    (comp (ref "TX")
      (value "TESTPAD_TPSQB1,27")
      (footprint "eagle-import:TESTPAD_B1,27")
      (libsource (lib "eagle-import") (part "TESTPAD_TPSQB1,27"))
    )
    (comp (ref "U1")
      (value "RP2040TR7")
      (footprint "eagle-import:RP2040TR7")
      (libsource (lib "eagle-import") (part "RP2040TR7"))
    )
    (comp (ref "U2")
      (value "MCP4725")
      (footprint "eagle-import:SOT23-6")
      (libsource (lib "eagle-import") (part "MCP4725SOT-23"))
    )
    (comp (ref "U3")
      (value "SN74AC14PWR")
      (footprint "eagle-import:TSSOP14")
      (libsource (lib "eagle-import") (part "7414"))
    )
    (comp (ref "U4")
      (value "MAX9938FEUK+T")
      (footprint "eagle-import:SOT95P280X145-5N")
      (libsource (lib "eagle-import") (part "MAX9938FEUK+T"))
    )
    (comp (ref "U5")
      (value "W25Q64JVSSIQ")
      (footprint "eagle-import:SOIC127P790X216-8N")
      (fields (field (name "MOUSER_PART_NUMBER") "454-W25Q64JVSSIQ"))
      (libsource (lib "eagle-import") (part "W25Q64JVSSIQ"))
    )
    (comp (ref "U6")
      (value "SN74AC14PWR")
      (footprint "eagle-import:TSSOP14")
      (libsource (lib "eagle-import") (part "7414"))
    )
    (comp (ref "U7")
      (value "TPIC2810D")
      (footprint "eagle-import:SO16")
      (libsource (lib "eagle-import") (part "TPIC2810D"))
    )
    (comp (ref "U8")
      (value "LM4040C30FTA")
      (footprint "eagle-import:SOT96P240X120-3N")
      (fields (field (name "MOUSER_PART_NUMBER") "621-LM4040C30FTA"))
      (libsource (lib "eagle-import") (part "LM4040C30FTA"))
    )
    (comp (ref "U11")
      (value "AP63203")
      (footprint "eagle-import:SOT95P280X100-6N")
      (fields
        (field (name "ARROW_PART_NUMBER") "AP63201WU-7")
        (field (name "MOUSER_PART_NUMBER") "621-AP63201WU-7")
      )
      (libsource (lib "eagle-import") (part "AP63201WU-7"))
    )
    (comp (ref "U12")
      (value "AP64501SP-13")
      (footprint "eagle-import:SOIC127P600X163-9N")
      (fields (field (name "MOUSER_PART_NUMBER") "621-AP64501SP-13"))
      (libsource (lib "eagle-import") (part "AP64501SP-13"))
    )
    (comp (ref "VBUS_SENSE")
      (value "TESTPAD_TPSQB1,27")
      (footprint "eagle-import:TESTPAD_B1,27")
      (libsource (lib "eagle-import") (part "TESTPAD_TPSQB1,27"))
    )
    (comp (ref "VOSEN")
      (value "TESTPAD_TPSQB1,27")
      (footprint "eagle-import:TESTPAD_B1,27")
      (libsource (lib "eagle-import") (part "TESTPAD_TPSQB1,27"))
    )
    (comp (ref "VOUT")
      (value "TESTPAD_TPSQB1,27")
      (footprint "eagle-import:TESTPAD_B1,27")
      (libsource (lib "eagle-import") (part "TESTPAD_TPSQB1,27"))
    )
    (comp (ref "X1")
      (value "ABM3C-12.000MHZ-D4Y-T")
      (footprint "eagle-import:ABM3C16000MHZD4YT")
      (fields (field (name "MOUSER_PART_NUMBER") "815-ABM3C-12-D4YT"))
      (libsource (lib "eagle-import") (part "ABM3C-12.000MHZ-D4Y-T"))
    )
  )
  (nets
    (net (code "1") (name "/3V_REF") (class "Default")
      (node (ref "C66") (pin "2") (pinfunction "2_2") (pintype "passive"))
      (node (ref "R57") (pin "1") (pinfunction "1_1") (pintype "passive"))
      (node (ref "U1") (pin "43") (pinfunction "ADC_AVDD_43") (pintype "bidirectional"))
      (node (ref "U8") (pin "1") (pinfunction "CATHODE_1") (pintype "bidirectional"))
    )
    (net (code "2") (name "/BUZZ") (class "Default")
      (node (ref "R28") (pin "1") (pinfunction "1_1") (pintype "passive"))
      (node (ref "U1") (pin "32") (pinfunction "GPIO21_32") (pintype "bidirectional"))
    )
    (net (code "3") (name "/CS") (class "Default")
      (node (ref "J6") (pin "7") (pinfunction "CS_7") (pintype "bidirectional"))
      (node (ref "R29") (pin "2") (pinfunction "2_2") (pintype "passive"))
      (node (ref "R66") (pin "2") (pinfunction "2_2") (pintype "passive"))
    )
    (net (code "4") (name "/D0") (class "Default")
      (node (ref "J6") (pin "3") (pinfunction "D0_3") (pintype "bidirectional"))
      (node (ref "R14") (pin "2") (pinfunction "2_2") (pintype "passive"))
    )
    (net (code "5") (name "/D1") (class "Default")
      (node (ref "J6") (pin "4") (pinfunction "D1_4") (pintype "bidirectional"))
      (node (ref "R17") (pin "2") (pinfunction "2_2") (pintype "passive"))
    )
    (net (code "6") (name "/DSP_RST") (class "Default")
      (node (ref "R21") (pin "1") (pinfunction "1_1") (pintype "passive"))
      (node (ref "U1") (pin "9") (pinfunction "GPIO7_9") (pintype "bidirectional"))
    )
    (net (code "7") (name "/EN_TPS54531") (class "Default")
      (node (ref "EN_TPS54531") (pin "TP") (pinfunction "TP_TP") (pintype "input"))
      (node (ref "Q4") (pin "2") (pinfunction "S_2") (pintype "passive"))
      (node (ref "R43") (pin "2") (pinfunction "2_2") (pintype "passive"))
      (node (ref "U12") (pin "3") (pinfunction "EN_3") (pintype "bidirectional"))
    )
    (net (code "8") (name "/FB") (class "Default")
      (node (ref "FB_ADJ") (pin "2") (pinfunction "2_2") (pintype "passive"))
      (node (ref "U11") (pin "1") (pinfunction "FB_1") (pintype "bidirectional"))
    )
    (net (code "9") (name "/FB_DAC") (class "Default")
      (node (ref "R30") (pin "1") (pinfunction "1_1") (pintype "passive"))
      (node (ref "U2") (pin "1") (pinfunction "VOUT_1") (pintype "bidirectional"))
    )
    (net (code "10") (name "/IN_OVC") (class "Default")
      (node (ref "IN_OVC") (pin "TP") (pinfunction "TP_TP") (pintype "input"))
      (node (ref "U6") (pin "13") (pinfunction "I_13") (pintype "input"))
    )
    (net (code "11") (name "/MISO") (class "Default")
      (node (ref "R24") (pin "1") (pinfunction "1_1") (pintype "passive"))
      (node (ref "U1") (pin "27") (pinfunction "GPIO16_27") (pintype "bidirectional"))
    )
    (net (code "12") (name "/MOSI") (class "Default")
      (node (ref "R17") (pin "1") (pinfunction "1_1") (pintype "passive"))
      (node (ref "U1") (pin "30") (pinfunction "GPIO19_30") (pintype "bidirectional"))
    )
    (net (code "13") (name "/N$41") (class "Default")
      (node (ref "N$41") (pin "TP") (pinfunction "TP_TP") (pintype "input"))
      (node (ref "OP1") (pin "2") (pinfunction "C_2") (pintype "passive"))
      (node (ref "R26") (pin "2") (pinfunction "2_2") (pintype "passive"))
    )
    (net (code "14") (name "/N$51") (class "Default")
      (node (ref "C29") (pin "2") (pinfunction "2_2") (pintype "passive"))
      (node (ref "D6") (pin "2") (pinfunction "K_2") (pintype "bidirectional"))
      (node (ref "L2") (pin "1") (pinfunction "1_1") (pintype "passive"))
      (node (ref "N$51") (pin "TP") (pinfunction "TP_TP") (pintype "input"))
      (node (ref "U12") (pin "8") (pinfunction "SW_8") (pintype "bidirectional"))
    )
    (net (code "15") (name "/OVC_ALARM") (class "Default")
      (node (ref "OVC_ALARM") (pin "TP") (pinfunction "TP_TP") (pintype "input"))
      (node (ref "U1") (pin "12") (pinfunction "GPIO9_12") (pintype "bidirectional"))
      (node (ref "U6") (pin "10") (pinfunction "O_10") (pintype "output"))
    )
    (net (code "16") (name "/PDL") (class "Default")
      (node (ref "C9") (pin "1") (pinfunction "1_1") (pintype "passive"))
      (node (ref "R18") (pin "2") (pinfunction "2_2") (pintype "passive"))
      (node (ref "R99") (pin "2") (pinfunction "2_2") (pintype "passive"))
      (node (ref "U6") (pin "1") (pinfunction "I_1") (pintype "input"))
    )
    (net (code "17") (name "/PEDAL") (class "Default")
      (node (ref "OP1") (pin "4") (pinfunction "COL_4") (pintype "passive"))
      (node (ref "R19") (pin "1") (pinfunction "1_1") (pintype "passive"))
      (node (ref "R99") (pin "1") (pinfunction "1_1") (pintype "passive"))
    )
    (net (code "18") (name "/PUSH") (class "Default")
      (node (ref "R65") (pin "1") (pinfunction "1_1") (pintype "passive"))
      (node (ref "U6") (pin "5") (pinfunction "I_5") (pintype "input"))
    )
    (net (code "19") (name "/PUSH_FILT") (class "Default")
      (node (ref "U1") (pin "5") (pinfunction "GPIO3_5") (pintype "bidirectional"))
      (node (ref "U6") (pin "8") (pinfunction "O_8") (pintype "output"))
    )
    (net (code "20") (name "/ROTA") (class "Default")
      (node (ref "C23") (pin "2") (pinfunction "2_2") (pintype "passive"))
      (node (ref "R53") (pin "1") (pinfunction "1_1") (pintype "passive"))
      (node (ref "S3") (pin "A1") (pinfunction "CHANNEL_A_A1") (pintype "bidirectional"))
      (node (ref "U3") (pin "5") (pinfunction "I_5") (pintype "input"))
    )
    (net (code "21") (name "/ROTA_FILT") (class "Default")
      (node (ref "U1") (pin "36") (pinfunction "GPIO24_36") (pintype "bidirectional"))
      (node (ref "U3") (pin "4") (pinfunction "O_4") (pintype "output"))
    )
    (net (code "22") (name "/ROTB") (class "Default")
      (node (ref "C22") (pin "2") (pinfunction "2_2") (pintype "passive"))
      (node (ref "R52") (pin "1") (pinfunction "1_1") (pintype "passive"))
      (node (ref "S3") (pin "B1") (pinfunction "CHANNEL_B_B1") (pintype "bidirectional"))
      (node (ref "U3") (pin "11") (pinfunction "I_11") (pintype "input"))
    )
    (net (code "23") (name "/ROTB_FILT") (class "Default")
      (node (ref "U1") (pin "15") (pinfunction "GPIO12_15") (pintype "bidirectional"))
      (node (ref "U3") (pin "8") (pinfunction "O_8") (pintype "output"))
    )
    (net (code "24") (name "/ROTPUSH") (class "Default")
      (node (ref "C24") (pin "2") (pinfunction "2_2") (pintype "passive"))
      (node (ref "R54") (pin "1") (pinfunction "1_1") (pintype "passive"))
      (node (ref "S3") (pin "2") (pinfunction "NO_2") (pintype "bidirectional"))
      (node (ref "U3") (pin "1") (pinfunction "I_1") (pintype "input"))
    )
    (net (code "25") (name "/RPUSH_FILT") (class "Default")
      (node (ref "U1") (pin "8") (pinfunction "GPIO6_8") (pintype "bidirectional"))
      (node (ref "U3") (pin "12") (pinfunction "O_12") (pintype "output"))
    )
    (net (code "26") (name "/RST") (class "Default")
      (node (ref "J6") (pin "5") (pinfunction "RST_5") (pintype "bidirectional"))
      (node (ref "R21") (pin "2") (pinfunction "2_2") (pintype "passive"))
    )
    (net (code "27") (name "/RUN") (class "Default")
      (node (ref "JP1") (pin "10") (pinfunction "10_10") (pintype "passive"))
      (node (ref "RUN") (pin "TP") (pinfunction "TP_TP") (pintype "input"))
      (node (ref "U1") (pin "26") (pinfunction "RUN_26") (pintype "bidirectional"))
    )
    (net (code "28") (name "/RX") (class "Default")
      (node (ref "RX") (pin "TP") (pinfunction "TP_TP") (pintype "input"))
      (node (ref "U1") (pin "3") (pinfunction "GPIO1_3") (pintype "bidirectional"))
    )
    (net (code "29") (name "/SCK") (class "Default")
      (node (ref "R14") (pin "1") (pinfunction "1_1") (pintype "passive"))
      (node (ref "U1") (pin "29") (pinfunction "GPIO18_29") (pintype "bidirectional"))
    )
    (net (code "30") (name "/SEL") (class "Default")
      (node (ref "U1") (pin "37") (pinfunction "GPIO25_37") (pintype "bidirectional"))
    )
    (net (code "31") (name "/SS") (class "Default")
      (node (ref "R29") (pin "1") (pinfunction "1_1") (pintype "passive"))
      (node (ref "U1") (pin "28") (pinfunction "GPIO17_28") (pintype "bidirectional"))
    )
    (net (code "32") (name "/SWCLK") (class "Default")
      (node (ref "JP1") (pin "4") (pinfunction "4_4") (pintype "passive"))
      (node (ref "SWCLK") (pin "TP") (pinfunction "TP_TP") (pintype "input"))
      (node (ref "U1") (pin "24") (pinfunction "SWCLK_24") (pintype "bidirectional"))
    )
    (net (code "33") (name "/SWDIO") (class "Default")
      (node (ref "JP1") (pin "2") (pinfunction "2_2") (pintype "passive"))
      (node (ref "SWDIO") (pin "TP") (pinfunction "TP_TP") (pintype "input"))
      (node (ref "U1") (pin "25") (pinfunction "SWDIO_25") (pintype "bidirectional"))
    )
    (net (code "34") (name "/SWO") (class "Default")
      (node (ref "JP1") (pin "6") (pinfunction "6_6") (pintype "passive"))
    )
    (net (code "35") (name "/TDI") (class "Default")
      (node (ref "JP1") (pin "8") (pinfunction "8_8") (pintype "passive"))
    )
    (net (code "36") (name "/TX") (class "Default")
      (node (ref "TX") (pin "TP") (pinfunction "TP_TP") (pintype "input"))
      (node (ref "U1") (pin "2") (pinfunction "GPIO0_2") (pintype "bidirectional"))
    )
    (net (code "37") (name "/USB_DM") (class "Default")
      (node (ref "U1") (pin "46") (pinfunction "USB_DM_46") (pintype "bidirectional"))
    )
    (net (code "38") (name "/USB_DP") (class "Default")
      (node (ref "U1") (pin "47") (pinfunction "USB_DP_47") (pintype "bidirectional"))
    )
    (net (code "39") (name "/VBUS_SENSE") (class "Default")
      (node (ref "C58") (pin "2") (pinfunction "2_2") (pintype "passive"))
      (node (ref "D7") (pin "3") (pinfunction "AC_3") (pintype "passive"))
      (node (ref "R50") (pin "1") (pinfunction "1_1") (pintype "passive"))
      (node (ref "R51") (pin "2") (pinfunction "2_2") (pintype "passive"))
      (node (ref "U1") (pin "38") (pinfunction "GPIO26_/_ADC0_38") (pintype "bidirectional"))
      (node (ref "VBUS_SENSE") (pin "TP") (pinfunction "TP_TP") (pintype "input"))
    )
    (net (code "40") (name "/VOSEN") (class "Default")
      (node (ref "C13") (pin "2") (pinfunction "2_2") (pintype "passive"))
      (node (ref "D2") (pin "3") (pinfunction "AC_3") (pintype "passive"))
      (node (ref "R36") (pin "1") (pinfunction "1_1") (pintype "passive"))
      (node (ref "R37") (pin "2") (pinfunction "2_2") (pintype "passive"))
      (node (ref "U1") (pin "40") (pinfunction "GPIO28_/_ADC2_40") (pintype "bidirectional"))
      (node (ref "VOSEN") (pin "TP") (pinfunction "TP_TP") (pintype "input"))
    )
    (net (code "41") (name "/VO_TPS") (class "Default")
      (node (ref "C19") (pin "2") (pinfunction "2_2") (pintype "passive"))
      (node (ref "C34") (pin "2") (pinfunction "2_2") (pintype "passive"))
      (node (ref "C39") (pin "1") (pinfunction "1_1") (pintype "passive"))
      (node (ref "C40") (pin "1") (pinfunction "1_1") (pintype "passive"))
      (node (ref "C41") (pin "1") (pinfunction "1_1") (pintype "passive"))
      (node (ref "C42") (pin "1") (pinfunction "1_1") (pintype "passive"))
      (node (ref "C43") (pin "1") (pinfunction "1_1") (pintype "passive"))
      (node (ref "L2") (pin "2") (pinfunction "2_2") (pintype "passive"))
      (node (ref "R11") (pin "2") (pinfunction "2_2") (pintype "passive"))
      (node (ref "R12") (pin "1") (pinfunction "1_1") (pintype "passive"))
      (node (ref "U4") (pin "5") (pinfunction "RS+_5") (pintype "power_in"))
    )
    (net (code "42") (name "1v1") (class "Default")
      (node (ref "C32") (pin "2") (pinfunction "2_2") (pintype "passive"))
      (node (ref "C33") (pin "2") (pinfunction "2_2") (pintype "passive"))
      (node (ref "C46") (pin "1") (pinfunction "1_1") (pintype "passive"))
      (node (ref "U1") (pin "23") (pinfunction "DVDD_1_23") (pintype "bidirectional"))
      (node (ref "U1") (pin "45") (pinfunction "VREG_VOUT_45") (pintype "bidirectional"))
      (node (ref "U1") (pin "50") (pinfunction "DVDD_2_50") (pintype "bidirectional"))
    )
    (net (code "43") (name "3V3MCU") (class "Default")
      (node (ref "3V3MCU") (pin "TP") (pinfunction "TP_TP") (pintype "input"))
      (node (ref "C1") (pin "2") (pinfunction "2_2") (pintype "passive"))
      (node (ref "C12") (pin "2") (pinfunction "2_2") (pintype "passive"))
      (node (ref "C15") (pin "1") (pinfunction "1_1") (pintype "passive"))
      (node (ref "C16") (pin "2") (pinfunction "2_2") (pintype "passive"))
      (node (ref "C2") (pin "2") (pinfunction "2_2") (pintype "passive"))
      (node (ref "C20") (pin "2") (pinfunction "2_2") (pintype "passive"))
      (node (ref "C25") (pin "2") (pinfunction "2_2") (pintype "passive"))
      (node (ref "C26") (pin "1") (pinfunction "1_1") (pintype "passive"))
      (node (ref "C3") (pin "2") (pinfunction "2_2") (pintype "passive"))
      (node (ref "C31") (pin "2") (pinfunction "2_2") (pintype "passive"))
      (node (ref "C44") (pin "2") (pinfunction "2_2") (pintype "passive"))
      (node (ref "C45") (pin "1") (pinfunction "1_1") (pintype "passive"))
      (node (ref "C5") (pin "2") (pinfunction "2_2") (pintype "passive"))
      (node (ref "C50") (pin "2") (pinfunction "2_2") (pintype "passive"))
      (node (ref "C51") (pin "2") (pinfunction "2_2") (pintype "passive"))
      (node (ref "C52") (pin "2") (pinfunction "2_2") (pintype "passive"))
      (node (ref "C53") (pin "2") (pinfunction "2_2") (pintype "passive"))
      (node (ref "C6") (pin "2") (pinfunction "2_2") (pintype "passive"))
      (node (ref "C60") (pin "2") (pinfunction "2_2") (pintype "passive"))
      (node (ref "C62") (pin "2") (pinfunction "2_2") (pintype "passive"))
      (node (ref "C7") (pin "2") (pinfunction "2_2") (pintype "passive"))
      (node (ref "C8") (pin "2") (pinfunction "2_2") (pintype "passive"))
      (node (ref "D2") (pin "2") (pinfunction "C_2") (pintype "passive"))
      (node (ref "D3") (pin "2") (pinfunction "C_2") (pintype "passive"))
      (node (ref "D7") (pin "2") (pinfunction "C_2") (pintype "passive"))
      (node (ref "DZ1") (pin "1") (pinfunction "K_1") (pintype "bidirectional"))
      (node (ref "J6") (pin "2") (pinfunction "VCC_2") (pintype "bidirectional"))
      (node (ref "JP1") (pin "1") (pinfunction "1_1") (pintype "passive"))
      (node (ref "L1") (pin "2") (pinfunction "2_2") (pintype "bidirectional"))
      (node (ref "LS1") (pin "1") (pinfunction "+_1") (pintype "bidirectional"))
      (node (ref "R13") (pin "2") (pinfunction "2_2") (pintype "passive"))
      (node (ref "R15") (pin "1") (pinfunction "1_1") (pintype "passive"))
      (node (ref "R19") (pin "2") (pinfunction "2_2") (pintype "passive"))
      (node (ref "R35") (pin "1") (pinfunction "1_1") (pintype "passive"))
      (node (ref "R40") (pin "2") (pinfunction "2_2") (pintype "passive"))
      (node (ref "R52") (pin "2") (pinfunction "2_2") (pintype "passive"))
      (node (ref "R53") (pin "2") (pinfunction "2_2") (pintype "passive"))
      (node (ref "R54") (pin "2") (pinfunction "2_2") (pintype "passive"))
      (node (ref "R57") (pin "2") (pinfunction "2_2") (pintype "passive"))
      (node (ref "R64") (pin "2") (pinfunction "2_2") (pintype "passive"))
      (node (ref "R66") (pin "1") (pinfunction "1_1") (pintype "passive"))
      (node (ref "R67") (pin "2") (pinfunction "2_2") (pintype "passive"))
      (node (ref "U1") (pin "1") (pinfunction "IOVDD_1_1") (pintype "bidirectional"))
      (node (ref "U1") (pin "10") (pinfunction "IOVDD_2_10") (pintype "bidirectional"))
      (node (ref "U1") (pin "22") (pinfunction "IOVDD_3_22") (pintype "bidirectional"))
      (node (ref "U1") (pin "33") (pinfunction "IOVDD_4_33") (pintype "bidirectional"))
      (node (ref "U1") (pin "42") (pinfunction "IOVDD_5_42") (pintype "bidirectional"))
      (node (ref "U1") (pin "44") (pinfunction "VREG_VIN_44") (pintype "bidirectional"))
      (node (ref "U1") (pin "48") (pinfunction "USB_VDD_48") (pintype "bidirectional"))
      (node (ref "U1") (pin "49") (pinfunction "IOVDD_6_49") (pintype "bidirectional"))
      (node (ref "U2") (pin "3") (pinfunction "VDD_3") (pintype "bidirectional"))
      (node (ref "U3") (pin "14") (pinfunction "VCC_14") (pintype "power_in"))
      (node (ref "U5") (pin "8") (pinfunction "VCC_8") (pintype "bidirectional"))
      (node (ref "U6") (pin "14") (pinfunction "VCC_14") (pintype "power_in"))
      (node (ref "U7") (pin "1") (pinfunction "VCC_1") (pintype "bidirectional"))
    )
    (net (code "44") (name "EN_DCDC") (class "Default")
      (node (ref "R27") (pin "2") (pinfunction "2_2") (pintype "passive"))
      (node (ref "R31") (pin "1") (pinfunction "1_1") (pintype "passive"))
      (node (ref "U1") (pin "4") (pinfunction "GPIO2_4") (pintype "bidirectional"))
    )
    (net (code "45") (name "GND") (class "Default")
      (node (ref "C1") (pin "1") (pinfunction "1_1") (pintype "passive"))
      (node (ref "C10") (pin "1") (pinfunction "1_1") (pintype "passive"))
      (node (ref "C11") (pin "1") (pinfunction "1_1") (pintype "passive"))
      (node (ref "C12") (pin "1") (pinfunction "1_1") (pintype "passive"))
      (node (ref "C13") (pin "1") (pinfunction "1_1") (pintype "passive"))
      (node (ref "C14") (pin "1") (pinfunction "1_1") (pintype "passive"))
      (node (ref "C15") (pin "2") (pinfunction "2_2") (pintype "passive"))
      (node (ref "C16") (pin "1") (pinfunction "1_1") (pintype "passive"))
      (node (ref "C17") (pin "2") (pinfunction "2_2") (pintype "passive"))
      (node (ref "C18") (pin "2") (pinfunction "2_2") (pintype "passive"))
      (node (ref "C2") (pin "1") (pinfunction "1_1") (pintype "passive"))
      (node (ref "C20") (pin "1") (pinfunction "1_1") (pintype "passive"))
      (node (ref "C21") (pin "2") (pinfunction "2_2") (pintype "passive"))
      (node (ref "C22") (pin "1") (pinfunction "1_1") (pintype "passive"))
      (node (ref "C23") (pin "1") (pinfunction "1_1") (pintype "passive"))
      (node (ref "C24") (pin "1") (pinfunction "1_1") (pintype "passive"))
      (node (ref "C25") (pin "1") (pinfunction "1_1") (pintype "passive"))
      (node (ref "C26") (pin "2") (pinfunction "2_2") (pintype "passive"))
      (node (ref "C27") (pin "1") (pinfunction "1_1") (pintype "passive"))
      (node (ref "C28") (pin "1") (pinfunction "1_1") (pintype "passive"))
      (node (ref "C3") (pin "1") (pinfunction "1_1") (pintype "passive"))
      (node (ref "C30") (pin "1") (pinfunction "1_1") (pintype "passive"))
      (node (ref "C31") (pin "1") (pinfunction "1_1") (pintype "passive"))
      (node (ref "C32") (pin "1") (pinfunction "1_1") (pintype "passive"))
      (node (ref "C33") (pin "1") (pinfunction "1_1") (pintype "passive"))
      (node (ref "C34") (pin "1") (pinfunction "1_1") (pintype "passive"))
      (node (ref "C35") (pin "2") (pinfunction "2_2") (pintype "passive"))
      (node (ref "C36") (pin "1") (pinfunction "1_1") (pintype "passive"))
      (node (ref "C38") (pin "1") (pinfunction "1_1") (pintype "passive"))
      (node (ref "C39") (pin "2") (pinfunction "2_2") (pintype "passive"))
      (node (ref "C40") (pin "2") (pinfunction "2_2") (pintype "passive"))
      (node (ref "C41") (pin "2") (pinfunction "2_2") (pintype "passive"))
      (node (ref "C42") (pin "2") (pinfunction "2_2") (pintype "passive"))
      (node (ref "C44") (pin "1") (pinfunction "1_1") (pintype "passive"))
      (node (ref "C45") (pin "2") (pinfunction "2_2") (pintype "passive"))
      (node (ref "C46") (pin "2") (pinfunction "2_2") (pintype "passive"))
      (node (ref "C47") (pin "1") (pinfunction "1_1") (pintype "passive"))
      (node (ref "C48") (pin "1") (pinfunction "1_1") (pintype "passive"))
      (node (ref "C49") (pin "1") (pinfunction "1_1") (pintype "passive"))
      (node (ref "C5") (pin "1") (pinfunction "1_1") (pintype "passive"))
      (node (ref "C50") (pin "1") (pinfunction "1_1") (pintype "passive"))
      (node (ref "C51") (pin "1") (pinfunction "1_1") (pintype "passive"))
      (node (ref "C53") (pin "1") (pinfunction "1_1") (pintype "passive"))
      (node (ref "C54") (pin "1") (pinfunction "1_1") (pintype "passive"))
      (node (ref "C58") (pin "1") (pinfunction "1_1") (pintype "passive"))
      (node (ref "C59") (pin "1") (pinfunction "1_1") (pintype "passive"))
      (node (ref "C6") (pin "1") (pinfunction "1_1") (pintype "passive"))
      (node (ref "C60") (pin "1") (pinfunction "1_1") (pintype "passive"))
      (node (ref "C61") (pin "1") (pinfunction "1_1") (pintype "passive"))
      (node (ref "C62") (pin "1") (pinfunction "1_1") (pintype "passive"))
      (node (ref "C63") (pin "1") (pinfunction "1_1") (pintype "passive"))
      (node (ref "C64") (pin "1") (pinfunction "1_1") (pintype "passive"))
      (node (ref "C65") (pin "1") (pinfunction "1_1") (pintype "passive"))
      (node (ref "C66") (pin "1") (pinfunction "1_1") (pintype "passive"))
      (node (ref "C7") (pin "1") (pinfunction "1_1") (pintype "passive"))
      (node (ref "C8") (pin "1") (pinfunction "1_1") (pintype "passive"))
      (node (ref "C9") (pin "2") (pinfunction "2_2") (pintype "passive"))
      (node (ref "D2") (pin "1") (pinfunction "A_1") (pintype "passive"))
      (node (ref "D6") (pin "1") (pinfunction "A_1") (pintype "bidirectional"))
      (node (ref "D7") (pin "1") (pinfunction "A_1") (pintype "passive"))
      (node (ref "D8") (pin "2") (pinfunction "A_2") (pintype "bidirectional"))
      (node (ref "DZ1") (pin "2") (pinfunction "A_2") (pintype "bidirectional"))
      (node (ref "GND") (pin "TP") (pinfunction "TP_TP") (pintype "input"))
      (node (ref "J6") (pin "1") (pinfunction "GND_1") (pintype "bidirectional"))
      (node (ref "JP1") (pin "3") (pinfunction "3_3") (pintype "passive"))
      (node (ref "JP1") (pin "5") (pinfunction "5_5") (pintype "passive"))
      (node (ref "JP1") (pin "7") (pinfunction "7_7") (pintype "passive"))
      (node (ref "JP1") (pin "9") (pinfunction "9_9") (pintype "passive"))
      (node (ref "OP1") (pin "3") (pinfunction "EMIT_3") (pintype "passive"))
      (node (ref "Q2") (pin "2") (pinfunction "S_2") (pintype "passive"))
      (node (ref "Q9") (pin "2") (pinfunction "S_2") (pintype "passive"))
      (node (ref "R16") (pin "2") (pinfunction "2_2") (pintype "passive"))
      (node (ref "R18") (pin "1") (pinfunction "1_1") (pintype "passive"))
      (node (ref "R22") (pin "2") (pinfunction "2_2") (pintype "passive"))
      (node (ref "R32") (pin "2") (pinfunction "2_2") (pintype "passive"))
      (node (ref "R36") (pin "2") (pinfunction "2_2") (pintype "passive"))
      (node (ref "R42") (pin "1") (pinfunction "1_1") (pintype "passive"))
      (node (ref "R43") (pin "1") (pinfunction "1_1") (pintype "passive"))
      (node (ref "R44") (pin "1") (pinfunction "1_1") (pintype "passive"))
      (node (ref "R45") (pin "1") (pinfunction "1_1") (pintype "passive"))
      (node (ref "R50") (pin "2") (pinfunction "2_2") (pintype "passive"))
      (node (ref "S2") (pin "2") (pinfunction "2_2") (pintype "passive"))
      (node (ref "S3") (pin "1") (pinfunction "COM_1") (pintype "bidirectional"))
      (node (ref "S3") (pin "C1") (pinfunction "COMMON_C1") (pintype "bidirectional"))
      (node (ref "U1") (pin "19") (pinfunction "TESTEN_19") (pintype "bidirectional"))
      (node (ref "U1") (pin "57") (pinfunction "GND_57") (pintype "bidirectional"))
      (node (ref "U11") (pin "4") (pinfunction "GND_4") (pintype "bidirectional"))
      (node (ref "U12") (pin "7") (pinfunction "GND_7") (pintype "bidirectional"))
      (node (ref "U12") (pin "9") (pinfunction "EP_9") (pintype "bidirectional"))
      (node (ref "U2") (pin "2") (pinfunction "VSS_2") (pintype "bidirectional"))
      (node (ref "U2") (pin "6") (pinfunction "AO_6") (pintype "bidirectional"))
      (node (ref "U3") (pin "7") (pinfunction "GND_7") (pintype "power_in"))
      (node (ref "U4") (pin "1") (pinfunction "GND_1") (pintype "passive"))
      (node (ref "U4") (pin "2") (pinfunction "GND_2_2") (pintype "passive"))
      (node (ref "U5") (pin "4") (pinfunction "GND_4") (pintype "bidirectional"))
      (node (ref "U6") (pin "7") (pinfunction "GND_7") (pintype "power_in"))
      (node (ref "U7") (pin "10") (pinfunction "A1_10") (pintype "bidirectional"))
      (node (ref "U7") (pin "16") (pinfunction "GND_16") (pintype "bidirectional"))
      (node (ref "U7") (pin "7") (pinfunction "A2_7") (pintype "bidirectional"))
      (node (ref "U7") (pin "8") (pinfunction "~{G}_8") (pintype "bidirectional"))
      (node (ref "U7") (pin "9") (pinfunction "A0_9") (pintype "bidirectional"))
      (node (ref "U8") (pin "2") (pinfunction "ANODE_1_2") (pintype "bidirectional"))
      (node (ref "X1") (pin "2") (pinfunction "GND_1_2") (pintype "bidirectional"))
      (node (ref "X1") (pin "4") (pinfunction "GND_2_4") (pintype "bidirectional"))
    )
    (net (code "46") (name "IN+") (class "Default")
      (node (ref "C36") (pin "2") (pinfunction "2_2") (pintype "passive"))
      (node (ref "IN+") (pin "TP") (pinfunction "TP_TP") (pintype "input"))
      (node (ref "PTC1") (pin "2") (pinfunction "2_2") (pintype "passive"))
      (node (ref "R51") (pin "1") (pinfunction "1_1") (pintype "passive"))
    )
    (net (code "47") (name "ISENSE") (class "Default")
      (node (ref "ISENSE") (pin "TP") (pinfunction "TP_TP") (pintype "input"))
      (node (ref "U1") (pin "39") (pinfunction "GPIO27_/_ADC1_39") (pintype "bidirectional"))
      (node (ref "U4") (pin "3") (pinfunction "OUT_3") (pintype "output"))
    )
    (net (code "48") (name "Net-(BZ1-+)") (class "Default")
      (node (ref "BZ1") (pin "1") (pinfunction "+_1") (pintype "passive"))
      (node (ref "C27") (pin "2") (pinfunction "2_2") (pintype "passive"))
      (node (ref "L7") (pin "2") (pinfunction "2_2") (pintype "passive"))
      (node (ref "R61") (pin "2") (pinfunction "2_2") (pintype "passive"))
    )
    (net (code "49") (name "Net-(BZ1--)") (class "Default")
      (node (ref "BZ1") (pin "2") (pinfunction "-_2") (pintype "passive"))
      (node (ref "D3") (pin "3") (pinfunction "AC_3") (pintype "passive"))
      (node (ref "LS1") (pin "2") (pinfunction "-_2") (pintype "bidirectional"))
      (node (ref "Q9") (pin "3") (pinfunction "D_3") (pintype "passive"))
      (node (ref "R61") (pin "1") (pinfunction "1_1") (pintype "passive"))
    )
    (net (code "50") (name "Net-(C10-Pad2)") (class "Default")
      (node (ref "C10") (pin "2") (pinfunction "2_2") (pintype "passive"))
      (node (ref "R13") (pin "1") (pinfunction "1_1") (pintype "passive"))
      (node (ref "R65") (pin "2") (pinfunction "2_2") (pintype "passive"))
      (node (ref "S2") (pin "4") (pinfunction "4_4") (pintype "passive"))
    )
    (net (code "51") (name "Net-(C37-Pad1)") (class "Default")
      (node (ref "C37") (pin "1") (pinfunction "1_1") (pintype "passive"))
      (node (ref "R44") (pin "2") (pinfunction "2_2") (pintype "passive"))
    )
    (net (code "52") (name "Net-(C52-Pad1)") (class "Default")
      (node (ref "C52") (pin "1") (pinfunction "1_1") (pintype "passive"))
      (node (ref "FB_ADJ") (pin "1") (pinfunction "1_1") (pintype "passive"))
      (node (ref "R15") (pin "2") (pinfunction "2_2") (pintype "passive"))
      (node (ref "R16") (pin "1") (pinfunction "1_1") (pintype "passive"))
    )
    (net (code "53") (name "Net-(D5-A)") (class "Default")
      (node (ref "D5") (pin "2") (pinfunction "A_2") (pintype "bidirectional"))
      (node (ref "OP1") (pin "1") (pinfunction "A_1") (pintype "passive"))
    )
    (net (code "54") (name "Net-(J6-DC)") (class "Default")
      (node (ref "J6") (pin "6") (pinfunction "DC_6") (pintype "bidirectional"))
      (node (ref "R24") (pin "2") (pinfunction "2_2") (pintype "passive"))
    )
    (net (code "55") (name "Net-(L3-Pad2)") (class "Default")
      (node (ref "L3") (pin "2") (pinfunction "2_2") (pintype "passive"))
      (node (ref "R26") (pin "1") (pinfunction "1_1") (pintype "passive"))
    )
    (net (code "56") (name "Net-(L4-Pad2)") (class "Default")
      (node (ref "L4") (pin "2") (pinfunction "2_2") (pintype "passive"))
      (node (ref "R22") (pin "1") (pinfunction "1_1") (pintype "passive"))
    )
    (net (code "57") (name "Net-(LED1-C)") (class "Default")
      (node (ref "LED1") (pin "K") (pinfunction "C_K") (pintype "passive"))
      (node (ref "Q2") (pin "3") (pinfunction "D_3") (pintype "passive"))
    )
    (net (code "58") (name "Net-(LED1-PadA)") (class "Default")
      (node (ref "LED1") (pin "A") (pinfunction "A_A") (pintype "passive"))
      (node (ref "R35") (pin "2") (pinfunction "2_2") (pintype "passive"))
    )
    (net (code "59") (name "Net-(Q2-G)") (class "Default")
      (node (ref "Q2") (pin "1") (pinfunction "G_1") (pintype "passive"))
      (node (ref "R31") (pin "2") (pinfunction "2_2") (pintype "passive"))
    )
    (net (code "60") (name "Net-(Q4-D)") (class "Default")
      (node (ref "Q4") (pin "3") (pinfunction "D_3") (pintype "passive"))
      (node (ref "R41") (pin "1") (pinfunction "1_1") (pintype "passive"))
    )
    (net (code "61") (name "Net-(Q4-G)") (class "Default")
      (node (ref "Q4") (pin "1") (pinfunction "G_1") (pintype "passive"))
      (node (ref "R27") (pin "1") (pinfunction "1_1") (pintype "passive"))
      (node (ref "R42") (pin "2") (pinfunction "2_2") (pintype "passive"))
    )
    (net (code "62") (name "Net-(Q9-G)") (class "Default")
      (node (ref "Q9") (pin "1") (pinfunction "G_1") (pintype "passive"))
      (node (ref "R28") (pin "2") (pinfunction "2_2") (pintype "passive"))
      (node (ref "R32") (pin "1") (pinfunction "1_1") (pintype "passive"))
    )
    (net (code "63") (name "Net-(U2-SCL)") (class "Default")
      (node (ref "R58") (pin "2") (pinfunction "2_2") (pintype "passive"))
      (node (ref "U2") (pin "5") (pinfunction "SCL_5") (pintype "bidirectional"))
    )
    (net (code "64") (name "Net-(U2-SDA)") (class "Default")
      (node (ref "R60") (pin "2") (pinfunction "2_2") (pintype "passive"))
      (node (ref "U2") (pin "4") (pinfunction "SDA_4") (pintype "bidirectional"))
    )
    (net (code "65") (name "Net-(U3A-I)") (class "Default")
      (node (ref "C49") (pin "2") (pinfunction "2_2") (pintype "passive"))
      (node (ref "R25") (pin "2") (pinfunction "2_2") (pintype "passive"))
      (node (ref "U3") (pin "13") (pinfunction "I_13") (pintype "input"))
    )
    (net (code "66") (name "Net-(U3B-O)") (class "Default")
      (node (ref "R2") (pin "1") (pinfunction "1_1") (pintype "passive"))
      (node (ref "U3") (pin "10") (pinfunction "O_10") (pintype "output"))
    )
    (net (code "67") (name "Net-(U3C-I)") (class "Default")
      (node (ref "C47") (pin "2") (pinfunction "2_2") (pintype "passive"))
      (node (ref "R2") (pin "2") (pinfunction "2_2") (pintype "passive"))
      (node (ref "U3") (pin "9") (pinfunction "I_9") (pintype "input"))
    )
    (net (code "68") (name "Net-(U3D-O)") (class "Default")
      (node (ref "R25") (pin "1") (pinfunction "1_1") (pintype "passive"))
      (node (ref "U3") (pin "2") (pinfunction "O_2") (pintype "output"))
    )
    (net (code "69") (name "Net-(U3E-I)") (class "Default")
      (node (ref "C48") (pin "2") (pinfunction "2_2") (pintype "passive"))
      (node (ref "R20") (pin "2") (pinfunction "2_2") (pintype "passive"))
      (node (ref "U3") (pin "3") (pinfunction "I_3") (pintype "input"))
    )
    (net (code "70") (name "Net-(U3F-O)") (class "Default")
      (node (ref "R20") (pin "1") (pinfunction "1_1") (pintype "passive"))
      (node (ref "U3") (pin "6") (pinfunction "O_6") (pintype "output"))
    )
    (net (code "71") (name "Net-(U4-RS-)") (class "Default")
      (node (ref "C43") (pin "2") (pinfunction "2_2") (pintype "passive"))
      (node (ref "R1") (pin "1") (pinfunction "1_1") (pintype "passive"))
      (node (ref "U4") (pin "4") (pinfunction "RS-_4") (pintype "input"))
    )
    (net (code "72") (name "Net-(U6A-O)") (class "Default")
      (node (ref "R39") (pin "1") (pinfunction "1_1") (pintype "passive"))
      (node (ref "U6") (pin "12") (pinfunction "O_12") (pintype "output"))
    )
    (net (code "73") (name "Net-(U6B-I)") (class "Default")
      (node (ref "C54") (pin "2") (pinfunction "2_2") (pintype "passive"))
      (node (ref "R39") (pin "2") (pinfunction "2_2") (pintype "passive"))
      (node (ref "U6") (pin "11") (pinfunction "I_11") (pintype "input"))
    )
    (net (code "74") (name "Net-(U6C-I)") (class "Default")
      (node (ref "C14") (pin "2") (pinfunction "2_2") (pintype "passive"))
      (node (ref "R33") (pin "2") (pinfunction "2_2") (pintype "passive"))
      (node (ref "U6") (pin "9") (pinfunction "I_9") (pintype "input"))
    )
    (net (code "75") (name "Net-(U6D-O)") (class "Default")
      (node (ref "R23") (pin "1") (pinfunction "1_1") (pintype "passive"))
      (node (ref "U6") (pin "2") (pinfunction "O_2") (pintype "output"))
    )
    (net (code "76") (name "Net-(U6E-I)") (class "Default")
      (node (ref "C11") (pin "2") (pinfunction "2_2") (pintype "passive"))
      (node (ref "R23") (pin "2") (pinfunction "2_2") (pintype "passive"))
      (node (ref "U6") (pin "3") (pinfunction "I_3") (pintype "input"))
    )
    (net (code "77") (name "Net-(U6F-O)") (class "Default")
      (node (ref "R33") (pin "1") (pinfunction "1_1") (pintype "passive"))
      (node (ref "U6") (pin "6") (pinfunction "O_6") (pintype "output"))
    )
    (net (code "78") (name "Net-(U7-DRAIN0)") (class "Default")
      (node (ref "R6") (pin "1") (pinfunction "1_1") (pintype "passive"))
      (node (ref "U7") (pin "3") (pinfunction "DRAIN0_3") (pintype "bidirectional"))
    )
    (net (code "79") (name "Net-(U7-DRAIN1)") (class "Default")
      (node (ref "R5") (pin "1") (pinfunction "1_1") (pintype "passive"))
      (node (ref "U7") (pin "4") (pinfunction "DRAIN1_4") (pintype "bidirectional"))
    )
    (net (code "80") (name "Net-(U7-DRAIN2)") (class "Default")
      (node (ref "R4") (pin "1") (pinfunction "1_1") (pintype "passive"))
      (node (ref "U7") (pin "5") (pinfunction "DRAIN2_5") (pintype "bidirectional"))
    )
    (net (code "81") (name "Net-(U7-DRAIN3)") (class "Default")
      (node (ref "R3") (pin "1") (pinfunction "1_1") (pintype "passive"))
      (node (ref "U7") (pin "6") (pinfunction "DRAIN3_6") (pintype "bidirectional"))
    )
    (net (code "82") (name "Net-(U7-DRAIN4)") (class "Default")
      (node (ref "R10") (pin "1") (pinfunction "1_1") (pintype "passive"))
      (node (ref "U7") (pin "11") (pinfunction "DRAIN4_11") (pintype "bidirectional"))
    )
    (net (code "83") (name "Net-(U7-DRAIN5)") (class "Default")
      (node (ref "R9") (pin "1") (pinfunction "1_1") (pintype "passive"))
      (node (ref "U7") (pin "12") (pinfunction "DRAIN5_12") (pintype "bidirectional"))
    )
    (net (code "84") (name "Net-(U7-DRAIN6)") (class "Default")
      (node (ref "R8") (pin "1") (pinfunction "1_1") (pintype "passive"))
      (node (ref "U7") (pin "13") (pinfunction "DRAIN6_13") (pintype "bidirectional"))
    )
    (net (code "85") (name "Net-(U7-DRAIN7)") (class "Default")
      (node (ref "R7") (pin "1") (pinfunction "1_1") (pintype "passive"))
      (node (ref "U7") (pin "14") (pinfunction "DRAIN7_14") (pintype "bidirectional"))
    )
    (net (code "86") (name "Net-(U7-SCL)") (class "Default")
      (node (ref "L5") (pin "1") (pinfunction "1_1") (pintype "passive"))
      (node (ref "U7") (pin "15") (pinfunction "SCL_15") (pintype "bidirectional"))
    )
    (net (code "87") (name "Net-(U7-SDA)") (class "Default")
      (node (ref "L6") (pin "1") (pinfunction "1_1") (pintype "passive"))
      (node (ref "U7") (pin "2") (pinfunction "SDA_2") (pintype "bidirectional"))
    )
    (net (code "88") (name "Net-(U11-BST)") (class "Default")
      (node (ref "C4") (pin "2") (pinfunction "2_2") (pintype "passive"))
      (node (ref "U11") (pin "6") (pinfunction "BST_6") (pintype "bidirectional"))
    )
    (net (code "89") (name "Net-(U11-SW)") (class "Default")
      (node (ref "C4") (pin "1") (pinfunction "1_1") (pintype "passive"))
      (node (ref "L1") (pin "1") (pinfunction "1_1") (pintype "bidirectional"))
      (node (ref "U11") (pin "5") (pinfunction "SW_5") (pintype "bidirectional"))
    )
    (net (code "90") (name "Net-(U12-BST)") (class "Default")
      (node (ref "C29") (pin "1") (pinfunction "1_1") (pintype "passive"))
      (node (ref "U12") (pin "1") (pinfunction "BST_1") (pintype "bidirectional"))
    )
    (net (code "91") (name "Net-(U12-COMP)") (class "Default")
      (node (ref "C37") (pin "2") (pinfunction "2_2") (pintype "passive"))
      (node (ref "C38") (pin "2") (pinfunction "2_2") (pintype "passive"))
      (node (ref "U12") (pin "6") (pinfunction "COMP_6") (pintype "bidirectional"))
    )
    (net (code "92") (name "Net-(U12-FB)") (class "Default")
      (node (ref "C19") (pin "1") (pinfunction "1_1") (pintype "passive"))
      (node (ref "C65") (pin "2") (pinfunction "2_2") (pintype "passive"))
      (node (ref "R10") (pin "2") (pinfunction "2_2") (pintype "passive"))
      (node (ref "R11") (pin "1") (pinfunction "1_1") (pintype "passive"))
      (node (ref "R3") (pin "2") (pinfunction "2_2") (pintype "passive"))
      (node (ref "R30") (pin "2") (pinfunction "2_2") (pintype "passive"))
      (node (ref "R4") (pin "2") (pinfunction "2_2") (pintype "passive"))
      (node (ref "R45") (pin "2") (pinfunction "2_2") (pintype "passive"))
      (node (ref "R5") (pin "2") (pinfunction "2_2") (pintype "passive"))
      (node (ref "R6") (pin "2") (pinfunction "2_2") (pintype "passive"))
      (node (ref "R7") (pin "2") (pinfunction "2_2") (pintype "passive"))
      (node (ref "R8") (pin "2") (pinfunction "2_2") (pintype "passive"))
      (node (ref "R9") (pin "2") (pinfunction "2_2") (pintype "passive"))
      (node (ref "U12") (pin "5") (pinfunction "FB_5") (pintype "bidirectional"))
    )
    (net (code "93") (name "Net-(U12-SS)") (class "Default")
      (node (ref "C30") (pin "2") (pinfunction "2_2") (pintype "passive"))
      (node (ref "U12") (pin "4") (pinfunction "SS_4") (pintype "bidirectional"))
    )
    (net (code "94") (name "Net-(X1-CRYSTAL_2)") (class "Default")
      (node (ref "C61") (pin "2") (pinfunction "2_2") (pintype "passive"))
      (node (ref "R46") (pin "2") (pinfunction "2_2") (pintype "passive"))
      (node (ref "X1") (pin "3") (pinfunction "CRYSTAL_2_3") (pintype "bidirectional"))
    )
    (net (code "95") (name "PEDAL+") (class "Default")
      (node (ref "L3") (pin "1") (pinfunction "1_1") (pintype "passive"))
      (node (ref "PEDAL+") (pin "TP") (pinfunction "TP_TP") (pintype "input"))
    )
    (net (code "96") (name "PEDAL-") (class "Default")
      (node (ref "L4") (pin "1") (pinfunction "1_1") (pintype "passive"))
      (node (ref "PEDAL-") (pin "TP") (pinfunction "TP_TP") (pintype "input"))
    )
    (net (code "97") (name "PEDAL_IP") (class "Default")
      (node (ref "U1") (pin "11") (pinfunction "GPIO8_11") (pintype "bidirectional"))
      (node (ref "U6") (pin "4") (pinfunction "O_4") (pintype "output"))
    )
    (net (code "98") (name "QSPI_SCLK") (class "Default")
      (node (ref "U1") (pin "52") (pinfunction "QSPI_SCLK_52") (pintype "bidirectional"))
      (node (ref "U5") (pin "6") (pinfunction "CLK_6") (pintype "bidirectional"))
    )
    (net (code "99") (name "QSPI_SD0") (class "Default")
      (node (ref "U1") (pin "53") (pinfunction "QSPI_SD0_53") (pintype "bidirectional"))
      (node (ref "U5") (pin "5") (pinfunction "DI(IO0)_5") (pintype "bidirectional"))
    )
    (net (code "100") (name "QSPI_SD1") (class "Default")
      (node (ref "U1") (pin "55") (pinfunction "QSPI_SD1_55") (pintype "bidirectional"))
      (node (ref "U5") (pin "2") (pinfunction "DO(IO1)_2") (pintype "bidirectional"))
    )
    (net (code "101") (name "QSPI_SD2") (class "Default")
      (node (ref "U1") (pin "54") (pinfunction "QSPI_SD2_54") (pintype "bidirectional"))
      (node (ref "U5") (pin "3") (pinfunction "/WP_(IO2)_3") (pintype "bidirectional"))
    )
    (net (code "102") (name "QSPI_SD3") (class "Default")
      (node (ref "U1") (pin "51") (pinfunction "QSPI_SD3_51") (pintype "bidirectional"))
      (node (ref "U5") (pin "7") (pinfunction "/HOLD_OR_/RESET_(IO3)_7") (pintype "bidirectional"))
    )
    (net (code "103") (name "QSPI_SS") (class "Default")
      (node (ref "R40") (pin "1") (pinfunction "1_1") (pintype "passive"))
      (node (ref "U1") (pin "56") (pinfunction "QSPI_SS_N_56") (pintype "bidirectional"))
      (node (ref "U5") (pin "1") (pinfunction "/CS_1") (pintype "bidirectional"))
    )
    (net (code "104") (name "SCL") (class "Default")
      (node (ref "L5") (pin "2") (pinfunction "2_2") (pintype "passive"))
      (node (ref "R58") (pin "1") (pinfunction "1_1") (pintype "passive"))
      (node (ref "R67") (pin "1") (pinfunction "1_1") (pintype "passive"))
      (node (ref "SCL") (pin "TP") (pinfunction "TP_TP") (pintype "input"))
      (node (ref "U1") (pin "7") (pinfunction "GPIO5_7") (pintype "bidirectional"))
    )
    (net (code "105") (name "SDA") (class "Default")
      (node (ref "L6") (pin "2") (pinfunction "2_2") (pintype "passive"))
      (node (ref "R60") (pin "1") (pinfunction "1_1") (pintype "passive"))
      (node (ref "R64") (pin "1") (pinfunction "1_1") (pintype "passive"))
      (node (ref "SDA") (pin "TP") (pinfunction "TP_TP") (pintype "input"))
      (node (ref "U1") (pin "6") (pinfunction "GPIO4_6") (pintype "bidirectional"))
    )
    (net (code "106") (name "VCC") (class "Default")
      (node (ref "C17") (pin "1") (pinfunction "1_1") (pintype "passive"))
      (node (ref "C18") (pin "1") (pinfunction "1_1") (pintype "passive"))
      (node (ref "C21") (pin "1") (pinfunction "1_1") (pintype "passive"))
      (node (ref "C28") (pin "2") (pinfunction "2_2") (pintype "passive"))
      (node (ref "C35") (pin "1") (pinfunction "1_1") (pintype "passive"))
      (node (ref "C63") (pin "2") (pinfunction "2_2") (pintype "passive"))
      (node (ref "C64") (pin "2") (pinfunction "2_2") (pintype "passive"))
      (node (ref "D5") (pin "1") (pinfunction "K_1") (pintype "bidirectional"))
      (node (ref "L7") (pin "1") (pinfunction "1_1") (pintype "passive"))
      (node (ref "PTC1") (pin "1") (pinfunction "1_1") (pintype "passive"))
      (node (ref "R41") (pin "2") (pinfunction "2_2") (pintype "passive"))
      (node (ref "U11") (pin "2") (pinfunction "EN_2") (pintype "bidirectional"))
      (node (ref "U11") (pin "3") (pinfunction "VIN_3") (pintype "bidirectional"))
      (node (ref "U12") (pin "2") (pinfunction "VIN_2") (pintype "bidirectional"))
    )
    (net (code "107") (name "VOUT") (class "Default")
      (node (ref "D8") (pin "1") (pinfunction "K_1") (pintype "bidirectional"))
      (node (ref "R1") (pin "2") (pinfunction "2_2") (pintype "passive"))
      (node (ref "R12") (pin "2") (pinfunction "2_2") (pintype "passive"))
      (node (ref "R37") (pin "1") (pinfunction "1_1") (pintype "passive"))
      (node (ref "VOUT") (pin "TP") (pinfunction "TP_TP") (pintype "input"))
    )
    (net (code "108") (name "XIN") (class "Default")
      (node (ref "C59") (pin "2") (pinfunction "2_2") (pintype "passive"))
      (node (ref "U1") (pin "20") (pinfunction "XIN_20") (pintype "bidirectional"))
      (node (ref "X1") (pin "1") (pinfunction "CRYSTAL_1_1") (pintype "bidirectional"))
    )
    (net (code "109") (name "XOUT") (class "Default")
      (node (ref "R46") (pin "1") (pinfunction "1_1") (pintype "passive"))
      (node (ref "U1") (pin "21") (pinfunction "XOUT_21") (pintype "bidirectional"))
    )
    (net (code "110") (name "unconnected-(D3-A-Pad1)") (class "Default")
      (node (ref "D3") (pin "1") (pinfunction "A_1") (pintype "passive"))
    )
    (net (code "111") (name "unconnected-(LS1-DUMMY-Pad3)") (class "Default")
      (node (ref "LS1") (pin "3") (pinfunction "DUMMY_3") (pintype "bidirectional"))
    )
    (net (code "112") (name "unconnected-(S2-Pad1)") (class "Default")
      (node (ref "S2") (pin "1") (pinfunction "1_1") (pintype "passive"))
    )
    (net (code "113") (name "unconnected-(S2-Pad3)") (class "Default")
      (node (ref "S2") (pin "3") (pinfunction "3_3") (pintype "passive"))
    )
    (net (code "114") (name "unconnected-(S3-PadMH1)") (class "Default")
      (node (ref "S3") (pin "MH1") (pinfunction "MH1_MH1") (pintype "bidirectional"))
    )
    (net (code "115") (name "unconnected-(S3-PadMH2)") (class "Default")
      (node (ref "S3") (pin "MH2") (pinfunction "MH2_MH2") (pintype "bidirectional"))
    )
    (net (code "116") (name "unconnected-(U1-GPIO10-Pad13)") (class "Default")
      (node (ref "U1") (pin "13") (pinfunction "GPIO10_13") (pintype "bidirectional"))
    )
    (net (code "117") (name "unconnected-(U1-GPIO11-Pad14)") (class "Default")
      (node (ref "U1") (pin "14") (pinfunction "GPIO11_14") (pintype "bidirectional"))
    )
    (net (code "118") (name "unconnected-(U1-GPIO13-Pad16)") (class "Default")
      (node (ref "U1") (pin "16") (pinfunction "GPIO13_16") (pintype "bidirectional"))
    )
    (net (code "119") (name "unconnected-(U1-GPIO14-Pad17)") (class "Default")
      (node (ref "U1") (pin "17") (pinfunction "GPIO14_17") (pintype "bidirectional"))
    )
    (net (code "120") (name "unconnected-(U1-GPIO15-Pad18)") (class "Default")
      (node (ref "U1") (pin "18") (pinfunction "GPIO15_18") (pintype "bidirectional"))
    )
    (net (code "121") (name "unconnected-(U1-GPIO20-Pad31)") (class "Default")
      (node (ref "U1") (pin "31") (pinfunction "GPIO20_31") (pintype "bidirectional"))
    )
    (net (code "122") (name "unconnected-(U1-GPIO22-Pad34)") (class "Default")
      (node (ref "U1") (pin "34") (pinfunction "GPIO22_34") (pintype "bidirectional"))
    )
    (net (code "123") (name "unconnected-(U1-GPIO23-Pad35)") (class "Default")
      (node (ref "U1") (pin "35") (pinfunction "GPIO23_35") (pintype "bidirectional"))
    )
    (net (code "124") (name "unconnected-(U1-GPIO29_{slash}_ADC3-Pad41)") (class "Default")
      (node (ref "U1") (pin "41") (pinfunction "GPIO29_/_ADC3_41") (pintype "bidirectional"))
    )
    (net (code "125") (name "unconnected-(U8-ANODE_2-Pad3)") (class "Default")
      (node (ref "U8") (pin "3") (pinfunction "ANODE_2_3") (pintype "bidirectional"))
    )
  )
)
